# humanoid-11.net
KiCad netlist of a schematic drawn in EAGLE
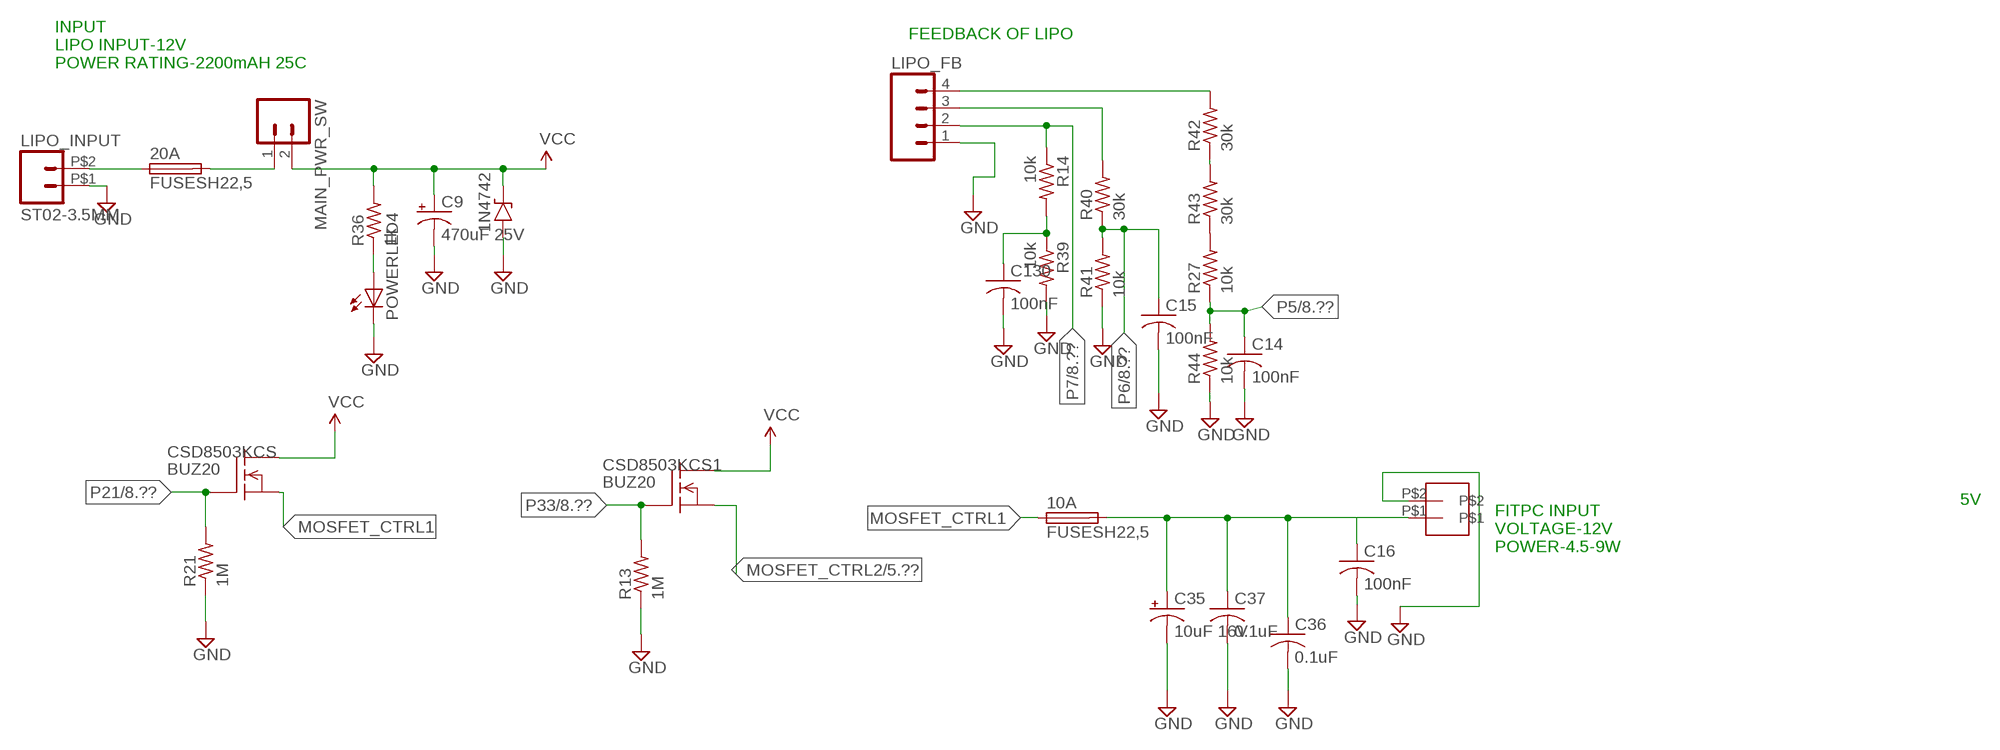
[diagram p0: schematic, sheet 1]
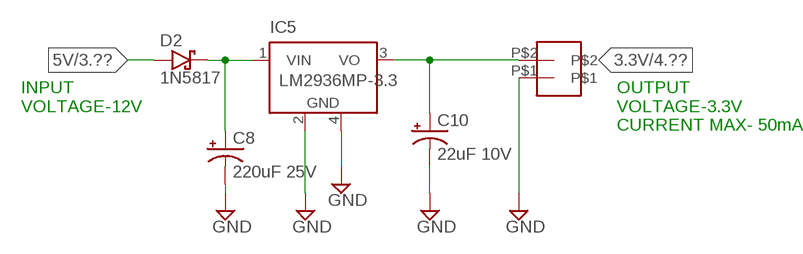
[diagram p1: schematic, sheet 2]
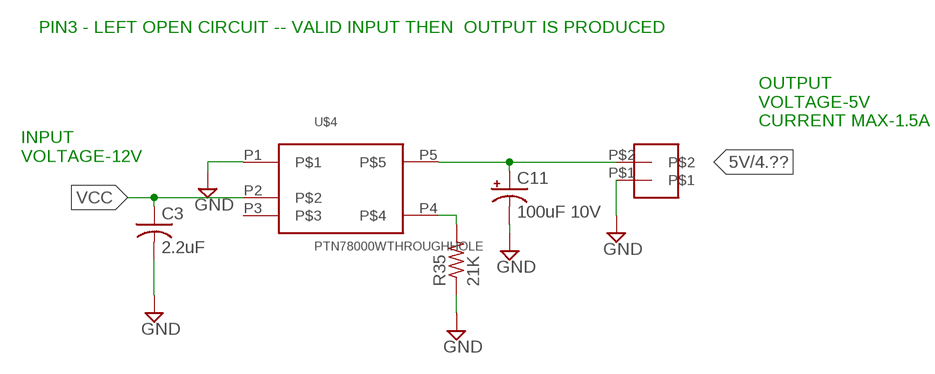
[diagram p2: schematic, sheet 3]
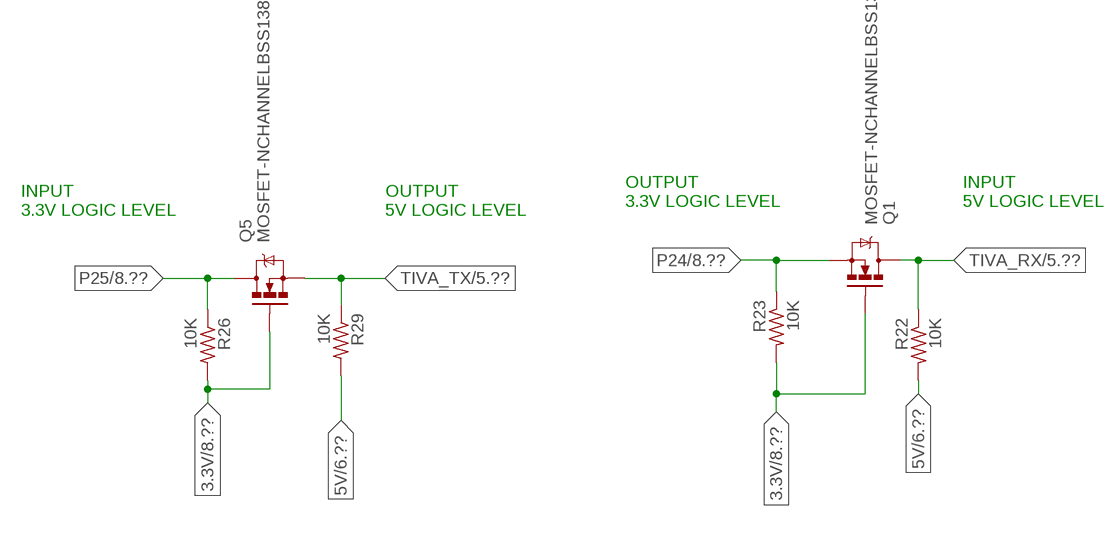
[diagram p3: schematic, sheet 4]
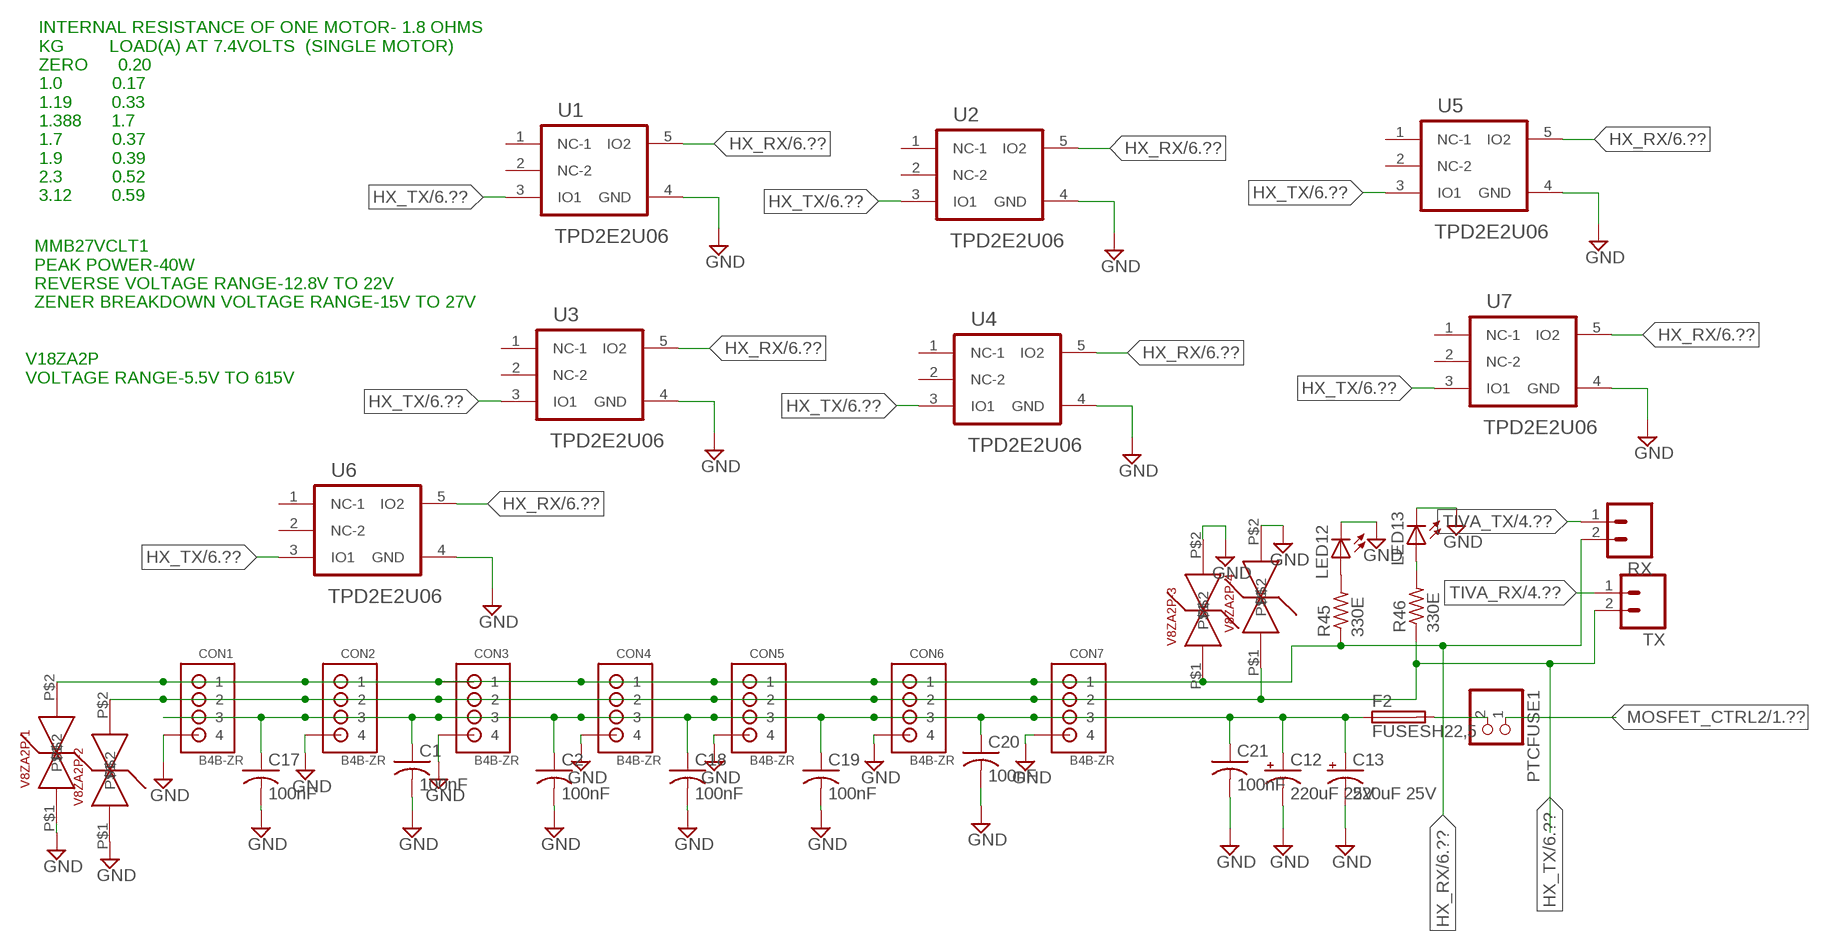
[diagram p4: schematic, sheet 5]
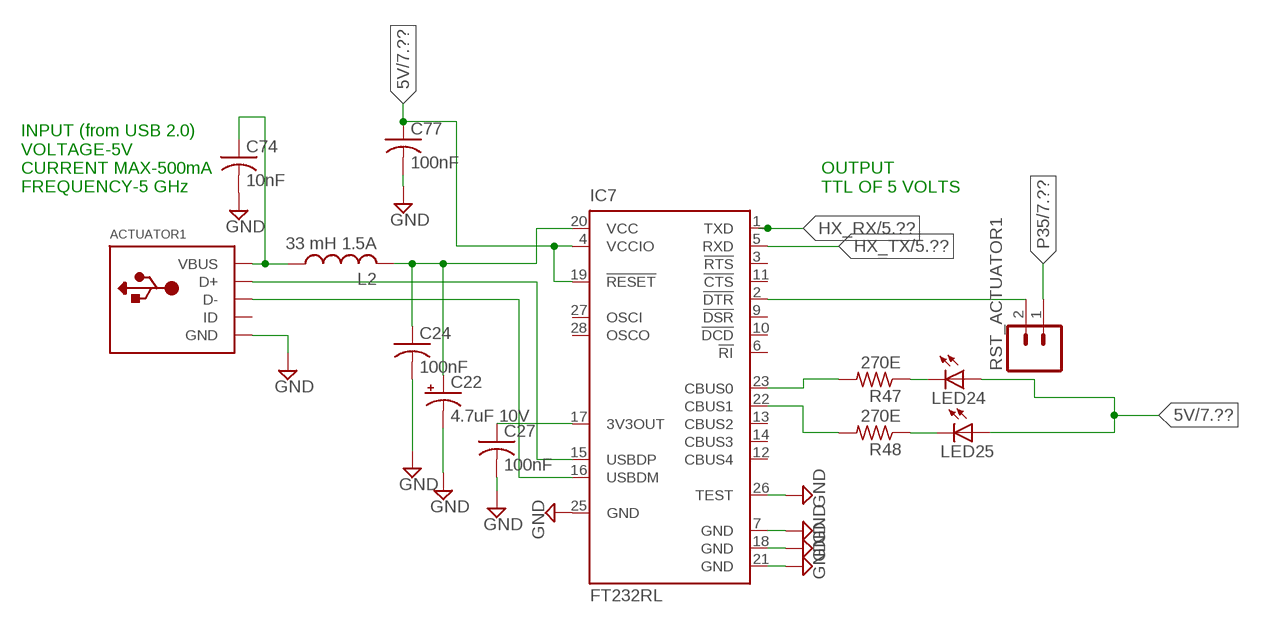
[diagram p5: schematic, sheet 6]
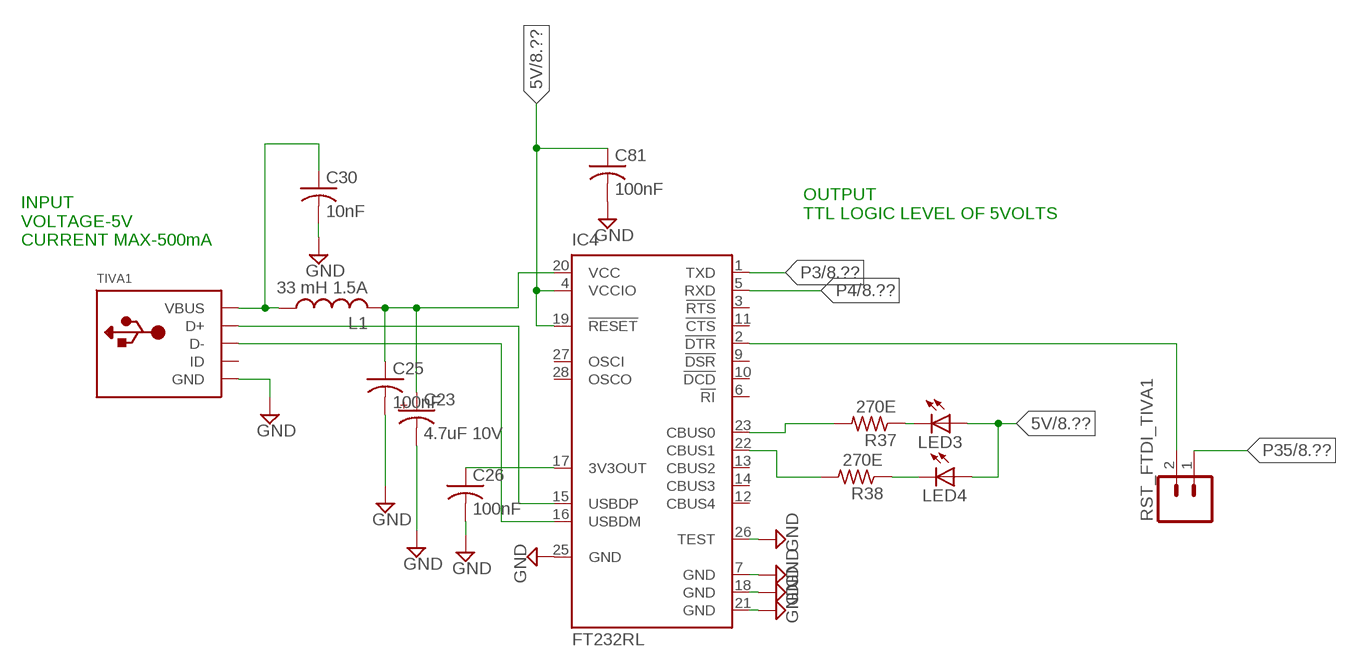
[diagram p6: schematic, sheet 7]
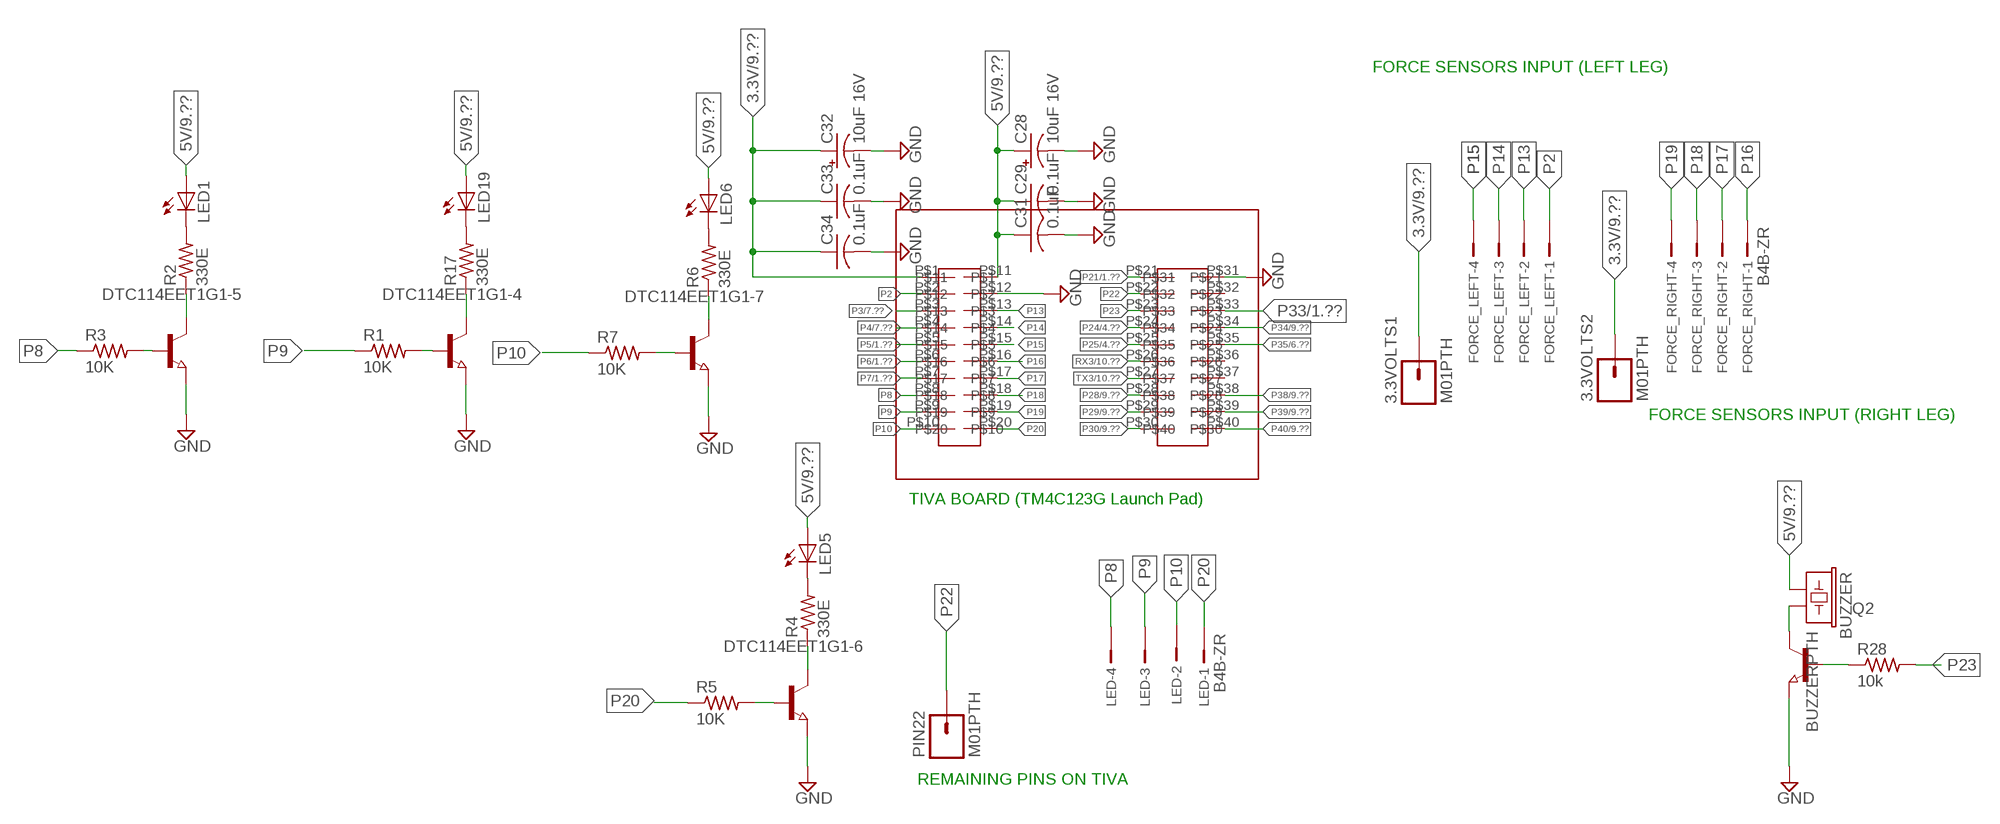
[diagram p7: schematic, sheet 8]
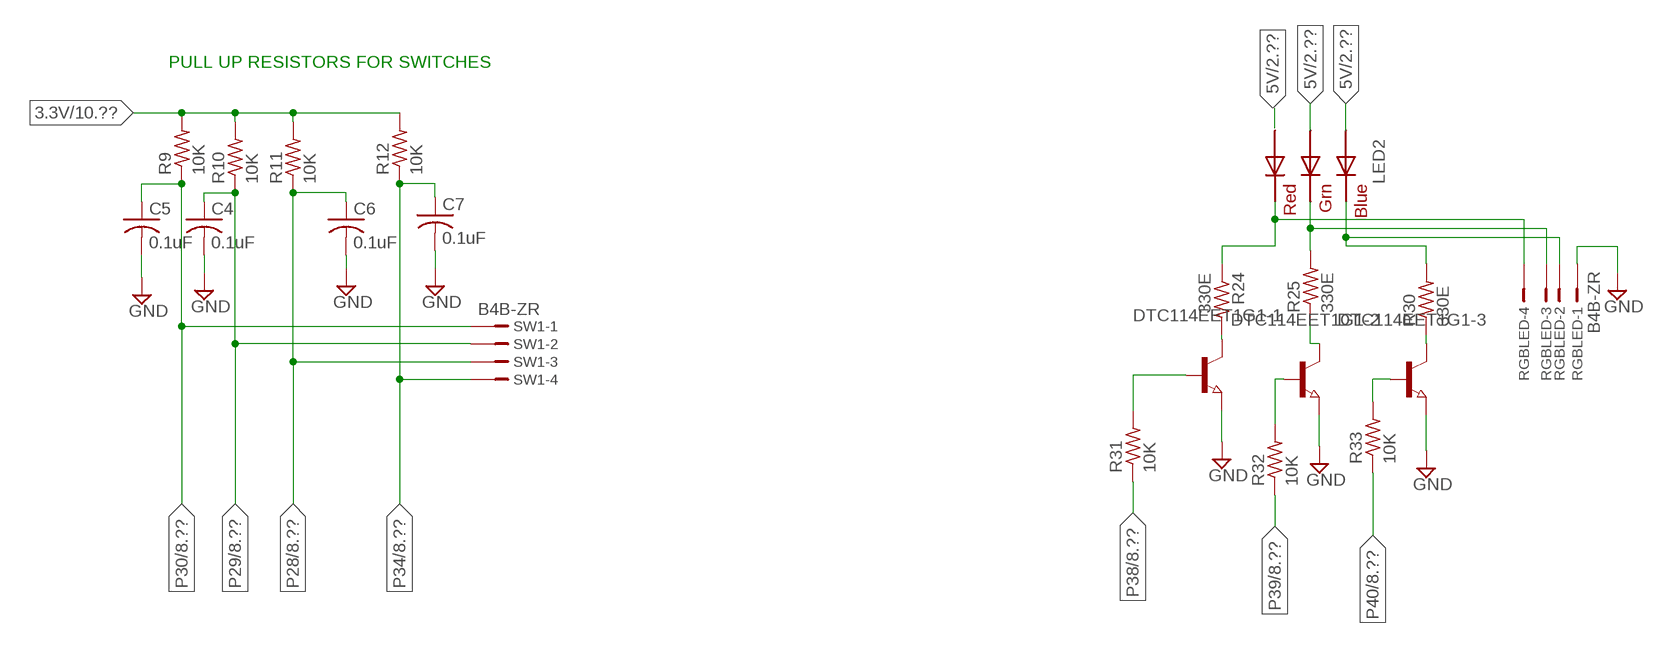
[diagram p8: schematic, sheet 9]
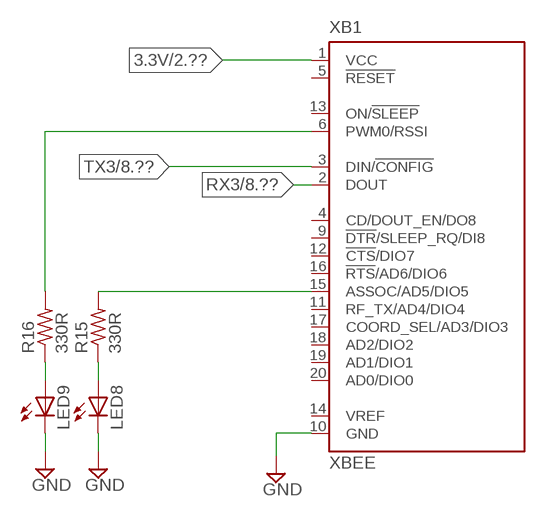
[diagram p9: schematic, sheet 10]

(export (version "E")
  (design (tool "Eeschema 10.0.6"))
  (components
    (comp (ref "5V1")
      (value "2PINRIGHT")
      (footprint "eagle-import:2PINRIGHT")
      (libsource (lib "eagle-import") (part "2PINRIGHT"))
    )
    (comp (ref "C3")
      (value "2.2uF")
      (footprint "eagle-import:C1608")
      (fields
        (field (name "MANUFACTURER") "TDK")
        (field (name "MOUSER_PARTNO") "810-C1608X7R1A225K")
        (field (name "PARTNO") "C1608X7R1A225K080AC")
      )
      (libsource (lib "eagle-import") (part "resistor_C-USC1608"))
    )
    (comp (ref "C11")
      (value "100uF 10V")
      (footprint "eagle-import:PANASONIC_E")
      (fields
        (field (name "MANUFACTURER") "Panasonic")
        (field (name "MOUSER_PARTNO") " 667-EEE-HA1A101P")
        (field (name "PARTNO") "EEE-HA1A101P")
      )
      (libsource (lib "eagle-import") (part "CPOL-USE"))
    )
    (comp (ref "R35")
      (value "21K")
      (footprint "eagle-import:R0805")
      (libsource (lib "eagle-import") (part "R-US_R0805"))
    )
    (comp (ref "U$4")
      (value "PTN78000WTHROUGHHOLE")
      (footprint "eagle-import:PTN78000W")
      (libsource (lib "eagle-import") (part "PTN78000WTHROUGHHOLE"))
    )
    (comp (ref "ACTUATOR1")
      (value "USBMINIB")
      (footprint "eagle-import:USB-MINIB")
      (libsource (lib "eagle-import") (part "USBMINIB"))
    )
    (comp (ref "C22")
      (value "4.7uF 10V")
      (footprint "eagle-import:PANASONIC_B")
      (fields
        (field (name "MANUFACTURER") "Panasonic")
        (field (name "MOUSER_PARTNO") "667-10SVP4R7M")
        (field (name "PARTNO") "10SVP4R7M")
      )
      (libsource (lib "eagle-import") (part "CPOL-USB"))
    )
    (comp (ref "C24")
      (value "100nF")
      (footprint "eagle-import:C1206")
      (fields (field (name "MANUFACTURER") "KEMET") (field (name "PARTNO") "C1206C104K5RACTU"))
      (libsource (lib "eagle-import") (part "C-USC1206"))
    )
    (comp (ref "C27")
      (value "100nF")
      (footprint "eagle-import:C1206")
      (fields (field (name "MANUFACTURER") "KEMET") (field (name "PARTNO") "C1206C104K5RACTU"))
      (libsource (lib "eagle-import") (part "C-USC1206"))
    )
    (comp (ref "C74")
      (value "10nF")
      (footprint "eagle-import:C1206")
      (libsource (lib "eagle-import") (part "C-USC1206"))
    )
    (comp (ref "C77")
      (value "100nF")
      (footprint "eagle-import:C1206")
      (libsource (lib "eagle-import") (part "C-USC1206"))
    )
    (comp (ref "IC7")
      (value "FT232RL")
      (footprint "eagle-import:SSOP28")
      (fields (field (name "OC_NEWARK") "unknown"))
      (libsource (lib "eagle-import") (part "FT232RL"))
    )
    (comp (ref "L2")
      (value "33 mH 1.5A")
      (footprint "eagle-import:L0805")
      (fields
        (field (name "MANUFACTURER") "Laird Technologies")
        (field (name "MOUSER_PARTNO") "875-MI0805K400R-10")
        (field (name "PARTNO") "MI0805K400R-10")
      )
      (libsource (lib "eagle-import") (part "L-USL0805"))
    )
    (comp (ref "LED24")
      (value "LEDCHIPLED_1206")
      (footprint "eagle-import:CHIPLED_1206")
      (libsource (lib "eagle-import") (part "LEDCHIPLED_1206"))
    )
    (comp (ref "LED25")
      (value "LEDCHIPLED_1206")
      (footprint "eagle-import:CHIPLED_1206")
      (libsource (lib "eagle-import") (part "LEDCHIPLED_1206"))
    )
    (comp (ref "R47")
      (value "270E")
      (footprint "eagle-import:R0805")
      (libsource (lib "eagle-import") (part "R-US_R0805"))
    )
    (comp (ref "R48")
      (value "270E")
      (footprint "eagle-import:R0805")
      (libsource (lib "eagle-import") (part "R-US_R0805"))
    )
    (comp (ref "RST_ACTUATOR1")
      (value "M02PTH")
      (footprint "eagle-import:1X02")
      (libsource (lib "eagle-import") (part "M02PTH"))
    )
    (comp (ref "3.3V1")
      (value "2PINRIGHT")
      (footprint "eagle-import:2PINRIGHT")
      (libsource (lib "eagle-import") (part "2PINRIGHT"))
    )
    (comp (ref "C8")
      (value "220uF 25V")
      (footprint "eagle-import:PANASONIC_G")
      (fields
        (field (name "MANUFACTURER") " PANASONIC ELECTRONIC COMPONENTS")
        (field (name "MOUSER_PARTNO") "667-EEE-1EA221P")
        (field (name "PARTNO") "EEE-1EA221P")
      )
      (libsource (lib "eagle-import") (part "CPOL-USG"))
    )
    (comp (ref "C10")
      (value "22uF 10V")
      (footprint "eagle-import:PANASONIC_B")
      (fields
        (field (name "MANUFACTURER") " PANASONIC ELECTRONIC COMPONENTS")
        (field (name "PARTNO") "EEEFK1A220AR")
      )
      (libsource (lib "eagle-import") (part "CPOL-USB"))
    )
    (comp (ref "D2")
      (value "1N5817")
      (footprint "eagle-import:DO41-3")
      (libsource (lib "eagle-import") (part "1N5817"))
    )
    (comp (ref "IC5")
      (value "LM2936MP-3.3")
      (footprint "eagle-import:SOT223")
      (fields
        (field (name "MF") "NATIONAL SEMICONDUCTOR")
        (field (name "MPN") "LM2936MP-3.3/NOPB")
        (field (name "OC_NEWARK") "unknown")
      )
      (libsource (lib "eagle-import") (part "LM2936MP?-3.3"))
    )
    (comp (ref "3.3VOLTS1")
      (value "M01PTH")
      (footprint "eagle-import:1X01")
      (libsource (lib "eagle-import") (part "M01PTH"))
    )
    (comp (ref "3.3VOLTS2")
      (value "M01PTH")
      (footprint "eagle-import:1X01")
      (libsource (lib "eagle-import") (part "M01PTH"))
    )
    (comp (ref "BUZZER")
      (value "BUZZERPTH")
      (footprint "eagle-import:BUZZER-12MM")
      (libsource (lib "eagle-import") (part "BUZZERPTH"))
    )
    (comp (ref "C28")
      (value "10uF 16V")
      (footprint "eagle-import:PANASONIC_B")
      (libsource (lib "eagle-import") (part "CPOL-USB"))
    )
    (comp (ref "C29")
      (value "0.1uF")
      (footprint "eagle-import:C0805")
      (libsource (lib "eagle-import") (part "resistor_C-USC0805"))
    )
    (comp (ref "C31")
      (value "0.1uF")
      (footprint "eagle-import:C0805")
      (libsource (lib "eagle-import") (part "resistor_C-USC0805"))
    )
    (comp (ref "C32")
      (value "10uF 16V")
      (footprint "eagle-import:PANASONIC_B")
      (libsource (lib "eagle-import") (part "CPOL-USB"))
    )
    (comp (ref "C33")
      (value "0.1uF")
      (footprint "eagle-import:C0805")
      (libsource (lib "eagle-import") (part "resistor_C-USC0805"))
    )
    (comp (ref "C34")
      (value "0.1uF")
      (footprint "eagle-import:C0805")
      (libsource (lib "eagle-import") (part "resistor_C-USC0805"))
    )
    (comp (ref "DTC114EET1G1-4")
      (value "NPN-TRANSISTOR_SOT23")
      (footprint "eagle-import:SOT23")
      (libsource (lib "eagle-import") (part "NPN-TRANSISTOR_SOT23"))
    )
    (comp (ref "DTC114EET1G1-5")
      (value "NPN-TRANSISTOR_SOT23")
      (footprint "eagle-import:SOT23")
      (libsource (lib "eagle-import") (part "NPN-TRANSISTOR_SOT23"))
    )
    (comp (ref "DTC114EET1G1-6")
      (value "NPN-TRANSISTOR_SOT23")
      (footprint "eagle-import:SOT23")
      (libsource (lib "eagle-import") (part "NPN-TRANSISTOR_SOT23"))
    )
    (comp (ref "DTC114EET1G1-7")
      (value "NPN-TRANSISTOR_SOT23")
      (footprint "eagle-import:SOT23")
      (libsource (lib "eagle-import") (part "NPN-TRANSISTOR_SOT23"))
    )
    (comp (ref "FORCE_LEFT")
      (value "B4B-ZR")
      (footprint "eagle-import:B4B-ZR")
      (fields
        (field (name "MF") "FARNELL")
        (field (name "MPN") "B4B-ZR(LF)(SN)")
        (field (name "OC_NEWARK") "unknown")
      )
      (libsource (lib "eagle-import") (part "?4B-ZRB"))
    )
    (comp (ref "FORCE_RIGHT")
      (value "B4B-ZR")
      (footprint "eagle-import:B4B-ZR")
      (fields
        (field (name "MF") "FARNELL")
        (field (name "MPN") "B4B-ZR(LF)(SN)")
        (field (name "OC_NEWARK") "unknown")
      )
      (libsource (lib "eagle-import") (part "?4B-ZRB"))
    )
    (comp (ref "LED")
      (value "B4B-ZR")
      (footprint "eagle-import:B4B-ZR")
      (fields
        (field (name "MF") "FARNELL")
        (field (name "MPN") "B4B-ZR(LF)(SN)")
        (field (name "OC_NEWARK") "unknown")
      )
      (libsource (lib "eagle-import") (part "?4B-ZRB"))
    )
    (comp (ref "LED1")
      (value "LEDCHIPLED_1206")
      (footprint "eagle-import:CHIPLED_1206")
      (libsource (lib "eagle-import") (part "LEDCHIPLED_1206"))
    )
    (comp (ref "LED5")
      (value "LEDCHIPLED_1206")
      (footprint "eagle-import:CHIPLED_1206")
      (libsource (lib "eagle-import") (part "LEDCHIPLED_1206"))
    )
    (comp (ref "LED6")
      (value "LEDCHIPLED_1206")
      (footprint "eagle-import:CHIPLED_1206")
      (libsource (lib "eagle-import") (part "LEDCHIPLED_1206"))
    )
    (comp (ref "LED19")
      (value "LEDCHIPLED_1206")
      (footprint "eagle-import:CHIPLED_1206")
      (libsource (lib "eagle-import") (part "LEDCHIPLED_1206"))
    )
    (comp (ref "PIN22")
      (value "M01PTH")
      (footprint "eagle-import:1X01")
      (libsource (lib "eagle-import") (part "M01PTH"))
    )
    (comp (ref "Q2")
      (value "NPN-TRANSISTOR_SOT23")
      (footprint "eagle-import:SOT23")
      (libsource (lib "eagle-import") (part "NPN-TRANSISTOR_SOT23"))
    )
    (comp (ref "R1")
      (value "10K")
      (footprint "eagle-import:R0805")
      (libsource (lib "eagle-import") (part "R-US_R0805"))
    )
    (comp (ref "R2")
      (value "330E")
      (footprint "eagle-import:R0805")
      (libsource (lib "eagle-import") (part "R-US_R0805"))
    )
    (comp (ref "R3")
      (value "10K")
      (footprint "eagle-import:R0805")
      (libsource (lib "eagle-import") (part "R-US_R0805"))
    )
    (comp (ref "R4")
      (value "330E")
      (footprint "eagle-import:R0805")
      (libsource (lib "eagle-import") (part "R-US_R0805"))
    )
    (comp (ref "R5")
      (value "10K")
      (footprint "eagle-import:R0805")
      (libsource (lib "eagle-import") (part "R-US_R0805"))
    )
    (comp (ref "R6")
      (value "330E")
      (footprint "eagle-import:R0805")
      (libsource (lib "eagle-import") (part "R-US_R0805"))
    )
    (comp (ref "R7")
      (value "10K")
      (footprint "eagle-import:R0805")
      (libsource (lib "eagle-import") (part "R-US_R0805"))
    )
    (comp (ref "R17")
      (value "330E")
      (footprint "eagle-import:R0805")
      (libsource (lib "eagle-import") (part "R-US_R0805"))
    )
    (comp (ref "R28")
      (value "10k")
      (footprint "eagle-import:R0805")
      (libsource (lib "eagle-import") (part "R-US_R0805"))
    )
    (comp (ref "U$1")
      (value "TIVA")
      (footprint "eagle-import:TIVA")
      (libsource (lib "eagle-import") (part "TIVA"))
    )
    (comp (ref "LED8")
      (value "LEDCHIPLED_1206")
      (footprint "eagle-import:CHIPLED_1206")
      (libsource (lib "eagle-import") (part "LEDCHIPLED_1206"))
    )
    (comp (ref "LED9")
      (value "LEDCHIPLED_1206")
      (footprint "eagle-import:CHIPLED_1206")
      (libsource (lib "eagle-import") (part "LEDCHIPLED_1206"))
    )
    (comp (ref "R15")
      (value "330R")
      (footprint "eagle-import:R0805")
      (libsource (lib "eagle-import") (part "R-US_R0805"))
    )
    (comp (ref "R16")
      (value "330R")
      (footprint "eagle-import:R0805")
      (libsource (lib "eagle-import") (part "R-US_R0805"))
    )
    (comp (ref "XB1")
      (value "XBEE")
      (footprint "eagle-import:XBEE")
      (fields (field (name "MPN") "XBP24-Z7UIT-004"))
      (libsource (lib "eagle-import") (part "XBEE"))
    )
    (comp (ref "Q1")
      (value "MOSFET-NCHANNELBSS138")
      (footprint "eagle-import:SOT23")
      (libsource (lib "eagle-import") (part "MOSFET-NCHANNELBSS138"))
    )
    (comp (ref "Q5")
      (value "MOSFET-NCHANNELBSS138")
      (footprint "eagle-import:SOT23")
      (libsource (lib "eagle-import") (part "MOSFET-NCHANNELBSS138"))
    )
    (comp (ref "R22")
      (value "10K")
      (footprint "eagle-import:R0805")
      (libsource (lib "eagle-import") (part "R-US_R0805"))
    )
    (comp (ref "R23")
      (value "10K")
      (footprint "eagle-import:R0805")
      (libsource (lib "eagle-import") (part "R-US_R0805"))
    )
    (comp (ref "R26")
      (value "10K")
      (footprint "eagle-import:R0805")
      (libsource (lib "eagle-import") (part "R-US_R0805"))
    )
    (comp (ref "R29")
      (value "10K")
      (footprint "eagle-import:R0805")
      (libsource (lib "eagle-import") (part "R-US_R0805"))
    )
    (comp (ref "C4")
      (value "0.1uF")
      (footprint "eagle-import:C1206")
      (fields
        (field (name "MANUFACTURER") "Kemet")
        (field (name "MOUSER_PARTNO") "80-C0805C104M5R")
        (field (name "PARTNO") "C0805C104M5RACTU")
      )
      (libsource (lib "eagle-import") (part "C-USC1206"))
    )
    (comp (ref "C5")
      (value "0.1uF")
      (footprint "eagle-import:C1206")
      (fields
        (field (name "MANUFACTURER") "Kemet")
        (field (name "MOUSER_PARTNO") "80-C0805C104M5R")
        (field (name "PARTNO") "C0805C104M5RACTU")
      )
      (libsource (lib "eagle-import") (part "C-USC1206"))
    )
    (comp (ref "C6")
      (value "0.1uF")
      (footprint "eagle-import:C1206")
      (fields
        (field (name "MANUFACTURER") "Kemet")
        (field (name "MOUSER_PARTNO") "80-C0805C104M5R")
        (field (name "PARTNO") "C0805C104M5RACTU")
      )
      (libsource (lib "eagle-import") (part "C-USC1206"))
    )
    (comp (ref "C7")
      (value "0.1uF")
      (footprint "eagle-import:C1206")
      (fields
        (field (name "MANUFACTURER") "Kemet")
        (field (name "MOUSER_PARTNO") "80-C0805C104M5R")
        (field (name "PARTNO") "C0805C104M5RACTU")
      )
      (libsource (lib "eagle-import") (part "C-USC1206"))
    )
    (comp (ref "DTC114EET1G1-1")
      (value "NPN-TRANSISTOR_SOT23")
      (footprint "eagle-import:SOT23")
      (libsource (lib "eagle-import") (part "NPN-TRANSISTOR_SOT23"))
    )
    (comp (ref "DTC114EET1G1-2")
      (value "NPN-TRANSISTOR_SOT23")
      (footprint "eagle-import:SOT23")
      (libsource (lib "eagle-import") (part "NPN-TRANSISTOR_SOT23"))
    )
    (comp (ref "DTC114EET1G1-3")
      (value "NPN-TRANSISTOR_SOT23")
      (footprint "eagle-import:SOT23")
      (libsource (lib "eagle-import") (part "NPN-TRANSISTOR_SOT23"))
    )
    (comp (ref "LED2")
      (value "RGBLED5050")
      (footprint "eagle-import:RGBLED5050")
      (libsource (lib "eagle-import") (part "RGBLED5050"))
    )
    (comp (ref "R9")
      (value "10K")
      (footprint "eagle-import:R0805")
      (libsource (lib "eagle-import") (part "R-US_R0805"))
    )
    (comp (ref "R10")
      (value "10K")
      (footprint "eagle-import:R0805")
      (libsource (lib "eagle-import") (part "R-US_R0805"))
    )
    (comp (ref "R11")
      (value "10K")
      (footprint "eagle-import:R0805")
      (libsource (lib "eagle-import") (part "R-US_R0805"))
    )
    (comp (ref "R12")
      (value "10K")
      (footprint "eagle-import:R0805")
      (libsource (lib "eagle-import") (part "R-US_R0805"))
    )
    (comp (ref "R24")
      (value "330E")
      (footprint "eagle-import:R0805")
      (libsource (lib "eagle-import") (part "R-US_R0805"))
    )
    (comp (ref "R25")
      (value "330E")
      (footprint "eagle-import:R0805")
      (libsource (lib "eagle-import") (part "R-US_R0805"))
    )
    (comp (ref "R30")
      (value "330E")
      (footprint "eagle-import:R0805")
      (libsource (lib "eagle-import") (part "R-US_R0805"))
    )
    (comp (ref "R31")
      (value "10K")
      (footprint "eagle-import:R0805")
      (libsource (lib "eagle-import") (part "R-US_R0805"))
    )
    (comp (ref "R32")
      (value "10K")
      (footprint "eagle-import:R0805")
      (libsource (lib "eagle-import") (part "R-US_R0805"))
    )
    (comp (ref "R33")
      (value "10K")
      (footprint "eagle-import:R0805")
      (libsource (lib "eagle-import") (part "R-US_R0805"))
    )
    (comp (ref "RGBLED")
      (value "B4B-ZR")
      (footprint "eagle-import:B4B-ZR")
      (fields
        (field (name "MF") "FARNELL")
        (field (name "MPN") "B4B-ZR(LF)(SN)")
        (field (name "OC_NEWARK") "unknown")
      )
      (libsource (lib "eagle-import") (part "?4B-ZRB"))
    )
    (comp (ref "SW1")
      (value "B4B-ZR")
      (footprint "eagle-import:B4B-ZR")
      (fields
        (field (name "MF") "FARNELL")
        (field (name "MPN") "B4B-ZR(LF)(SN)")
        (field (name "OC_NEWARK") "unknown")
      )
      (libsource (lib "eagle-import") (part "?4B-ZRB"))
    )
    (comp (ref "C23")
      (value "4.7uF 10V")
      (footprint "eagle-import:PANASONIC_B")
      (fields
        (field (name "MANUFACTURER") "Panasonic")
        (field (name "MOUSER_PARTNO") "667-10SVP4R7M")
        (field (name "PARTNO") "10SVP4R7M")
      )
      (libsource (lib "eagle-import") (part "CPOL-USB"))
    )
    (comp (ref "C25")
      (value "100nF")
      (footprint "eagle-import:C1206")
      (fields (field (name "MANUFACTURER") "KEMET") (field (name "PARTNO") "C1206C104K5RACTU"))
      (libsource (lib "eagle-import") (part "C-USC1206"))
    )
    (comp (ref "C26")
      (value "100nF")
      (footprint "eagle-import:C1206")
      (fields (field (name "MANUFACTURER") "KEMET") (field (name "PARTNO") "C1206C104K5RACTU"))
      (libsource (lib "eagle-import") (part "C-USC1206"))
    )
    (comp (ref "C30")
      (value "10nF")
      (footprint "eagle-import:C1206")
      (libsource (lib "eagle-import") (part "C-USC1206"))
    )
    (comp (ref "C81")
      (value "100nF")
      (footprint "eagle-import:C1206")
      (libsource (lib "eagle-import") (part "C-USC1206"))
    )
    (comp (ref "IC4")
      (value "FT232RL")
      (footprint "eagle-import:SSOP28")
      (fields (field (name "OC_NEWARK") "unknown"))
      (libsource (lib "eagle-import") (part "FT232RL"))
    )
    (comp (ref "L1")
      (value "33 mH 1.5A")
      (footprint "eagle-import:L0805")
      (fields
        (field (name "MANUFACTURER") "Laird Technologies")
        (field (name "MOUSER_PARTNO") "875-MI0805K400R-10")
        (field (name "PARTNO") "MI0805K400R-10")
      )
      (libsource (lib "eagle-import") (part "L-USL0805"))
    )
    (comp (ref "LED3")
      (value "LEDCHIPLED_1206")
      (footprint "eagle-import:CHIPLED_1206")
      (libsource (lib "eagle-import") (part "LEDCHIPLED_1206"))
    )
    (comp (ref "LED4")
      (value "LEDCHIPLED_1206")
      (footprint "eagle-import:CHIPLED_1206")
      (libsource (lib "eagle-import") (part "LEDCHIPLED_1206"))
    )
    (comp (ref "R37")
      (value "270E")
      (footprint "eagle-import:R0805")
      (libsource (lib "eagle-import") (part "R-US_R0805"))
    )
    (comp (ref "R38")
      (value "270E")
      (footprint "eagle-import:R0805")
      (libsource (lib "eagle-import") (part "R-US_R0805"))
    )
    (comp (ref "RST_FTDI_TIVA1")
      (value "M02PTH")
      (footprint "eagle-import:1X02")
      (libsource (lib "eagle-import") (part "M02PTH"))
    )
    (comp (ref "TIVA1")
      (value "USBMINIB")
      (footprint "eagle-import:USB-MINIB")
      (libsource (lib "eagle-import") (part "USBMINIB"))
    )
    (comp (ref "C1")
      (value "100nF")
      (footprint "eagle-import:C1206")
      (fields (field (name "MANUFACTURER") "KEMET") (field (name "PARTNO") "C1206C104K5RACTU"))
      (libsource (lib "eagle-import") (part "C-USC1206"))
    )
    (comp (ref "C2")
      (value "100nF")
      (footprint "eagle-import:C1206")
      (fields (field (name "MANUFACTURER") "KEMET") (field (name "PARTNO") "C1206C104K5RACTU"))
      (libsource (lib "eagle-import") (part "C-USC1206"))
    )
    (comp (ref "C12")
      (value "220uF 25V")
      (footprint "eagle-import:PANASONIC_G")
      (fields
        (field (name "MANUFACTURER") " PANASONIC ELECTRONIC COMPONENTS")
        (field (name "MOUSER_PARTNO") "667-EEE-1EA221P")
        (field (name "PARTNO") "EEE-1EA221P")
      )
      (libsource (lib "eagle-import") (part "CPOL-USG"))
    )
    (comp (ref "C13")
      (value "220uF 25V")
      (footprint "eagle-import:PANASONIC_G")
      (fields
        (field (name "MANUFACTURER") " PANASONIC ELECTRONIC COMPONENTS")
        (field (name "MOUSER_PARTNO") "667-EEE-1EA221P")
        (field (name "PARTNO") "EEE-1EA221P")
      )
      (libsource (lib "eagle-import") (part "CPOL-USG"))
    )
    (comp (ref "C17")
      (value "100nF")
      (footprint "eagle-import:C1206")
      (fields (field (name "MANUFACTURER") "KEMET") (field (name "PARTNO") "C1206C104K5RACTU"))
      (libsource (lib "eagle-import") (part "C-USC1206"))
    )
    (comp (ref "C18")
      (value "100nF")
      (footprint "eagle-import:C1206")
      (fields (field (name "MANUFACTURER") "KEMET") (field (name "PARTNO") "C1206C104K5RACTU"))
      (libsource (lib "eagle-import") (part "C-USC1206"))
    )
    (comp (ref "C19")
      (value "100nF")
      (footprint "eagle-import:C1206")
      (fields (field (name "MANUFACTURER") "KEMET") (field (name "PARTNO") "C1206C104K5RACTU"))
      (libsource (lib "eagle-import") (part "C-USC1206"))
    )
    (comp (ref "C20")
      (value "100nF")
      (footprint "eagle-import:C1206")
      (fields (field (name "MANUFACTURER") "KEMET") (field (name "PARTNO") "C1206C104K5RACTU"))
      (libsource (lib "eagle-import") (part "C-USC1206"))
    )
    (comp (ref "C21")
      (value "100nF")
      (footprint "eagle-import:C1206")
      (fields (field (name "MANUFACTURER") "KEMET") (field (name "PARTNO") "C1206C104K5RACTU"))
      (libsource (lib "eagle-import") (part "C-USC1206"))
    )
    (comp (ref "CON1")
      (value "B4B-ZR")
      (footprint "eagle-import:B4B-ZR")
      (fields (field (name "MF") "FARNELL") (field (name "MPN") "B4B-ZR(LF)(SN)"))
      (libsource (lib "eagle-import") (part "B4B-ZR"))
    )
    (comp (ref "CON2")
      (value "B4B-ZR")
      (footprint "eagle-import:B4B-ZR")
      (fields (field (name "MF") "FARNELL") (field (name "MPN") "B4B-ZR(LF)(SN)"))
      (libsource (lib "eagle-import") (part "B4B-ZR"))
    )
    (comp (ref "CON3")
      (value "B4B-ZR")
      (footprint "eagle-import:B4B-ZR")
      (fields (field (name "MF") "FARNELL") (field (name "MPN") "B4B-ZR(LF)(SN)"))
      (libsource (lib "eagle-import") (part "B4B-ZR"))
    )
    (comp (ref "CON4")
      (value "B4B-ZR")
      (footprint "eagle-import:B4B-ZR")
      (fields (field (name "MF") "FARNELL") (field (name "MPN") "B4B-ZR(LF)(SN)"))
      (libsource (lib "eagle-import") (part "B4B-ZR"))
    )
    (comp (ref "CON5")
      (value "B4B-ZR")
      (footprint "eagle-import:B4B-ZR")
      (fields (field (name "MF") "FARNELL") (field (name "MPN") "B4B-ZR(LF)(SN)"))
      (libsource (lib "eagle-import") (part "B4B-ZR"))
    )
    (comp (ref "CON6")
      (value "B4B-ZR")
      (footprint "eagle-import:B4B-ZR")
      (fields (field (name "MF") "FARNELL") (field (name "MPN") "B4B-ZR(LF)(SN)"))
      (libsource (lib "eagle-import") (part "B4B-ZR"))
    )
    (comp (ref "CON7")
      (value "B4B-ZR")
      (footprint "eagle-import:B4B-ZR")
      (fields (field (name "MF") "FARNELL") (field (name "MPN") "B4B-ZR(LF)(SN)"))
      (libsource (lib "eagle-import") (part "B4B-ZR"))
    )
    (comp (ref "F2")
      (value "FUSESH22,5")
      (footprint "eagle-import:SH22,5")
      (libsource (lib "eagle-import") (part "FUSESH22,5"))
    )
    (comp (ref "LED12")
      (value "LEDCHIPLED_1206")
      (footprint "eagle-import:CHIPLED_1206")
      (libsource (lib "eagle-import") (part "LEDCHIPLED_1206"))
    )
    (comp (ref "LED13")
      (value "LEDCHIPLED_1206")
      (footprint "eagle-import:CHIPLED_1206")
      (libsource (lib "eagle-import") (part "LEDCHIPLED_1206"))
    )
    (comp (ref "PTCFUSE1")
      (value "PINHD-1X2")
      (footprint "eagle-import:1X02")
      (libsource (lib "eagle-import") (part "PINHD-1X2"))
    )
    (comp (ref "R45")
      (value "330E")
      (footprint "eagle-import:R0805")
      (libsource (lib "eagle-import") (part "R-US_R0805"))
    )
    (comp (ref "R46")
      (value "330E")
      (footprint "eagle-import:R0805")
      (libsource (lib "eagle-import") (part "R-US_R0805"))
    )
    (comp (ref "RX")
      (value "M02PTH")
      (footprint "eagle-import:1X02")
      (libsource (lib "eagle-import") (part "M02PTH"))
    )
    (comp (ref "TX")
      (value "M02PTH")
      (footprint "eagle-import:1X02")
      (libsource (lib "eagle-import") (part "M02PTH"))
    )
    (comp (ref "U1")
      (value "TPD2E2U06")
      (footprint "eagle-import:SOT50P160X60-5N")
      (fields (field (name "MPN") "TPD2E001IDRLRQ1"))
      (libsource (lib "eagle-import") (part "TPD2E2U06"))
    )
    (comp (ref "U2")
      (value "TPD2E2U06")
      (footprint "eagle-import:SOT50P160X60-5N")
      (fields (field (name "MPN") "TPD2E001IDRLRQ1"))
      (libsource (lib "eagle-import") (part "TPD2E2U06"))
    )
    (comp (ref "U3")
      (value "TPD2E2U06")
      (footprint "eagle-import:SOT50P160X60-5N")
      (fields (field (name "MPN") "TPD2E001IDRLRQ1"))
      (libsource (lib "eagle-import") (part "TPD2E2U06"))
    )
    (comp (ref "U4")
      (value "TPD2E2U06")
      (footprint "eagle-import:SOT50P160X60-5N")
      (fields (field (name "MPN") "TPD2E001IDRLRQ1"))
      (libsource (lib "eagle-import") (part "TPD2E2U06"))
    )
    (comp (ref "U5")
      (value "TPD2E2U06")
      (footprint "eagle-import:SOT50P160X60-5N")
      (fields (field (name "MPN") "TPD2E001IDRLRQ1"))
      (libsource (lib "eagle-import") (part "TPD2E2U06"))
    )
    (comp (ref "U6")
      (value "TPD2E2U06")
      (footprint "eagle-import:SOT50P160X60-5N")
      (fields (field (name "MPN") "TPD2E001IDRLRQ1"))
      (libsource (lib "eagle-import") (part "TPD2E2U06"))
    )
    (comp (ref "U7")
      (value "TPD2E2U06")
      (footprint "eagle-import:SOT50P160X60-5N")
      (fields (field (name "MPN") "TPD2E001IDRLRQ1"))
      (libsource (lib "eagle-import") (part "TPD2E2U06"))
    )
    (comp (ref "V8ZA2P-1")
      (value "V18ZA2P")
      (footprint "eagle-import:V18ZA2P")
      (libsource (lib "eagle-import") (part "V18ZA2P"))
    )
    (comp (ref "V8ZA2P-2")
      (value "V18ZA2P")
      (footprint "eagle-import:V18ZA2P")
      (libsource (lib "eagle-import") (part "V18ZA2P"))
    )
    (comp (ref "V8ZA2P-3")
      (value "V18ZA2P")
      (footprint "eagle-import:V18ZA2P")
      (libsource (lib "eagle-import") (part "V18ZA2P"))
    )
    (comp (ref "V8ZA2P-4")
      (value "V18ZA2P")
      (footprint "eagle-import:V18ZA2P")
      (libsource (lib "eagle-import") (part "V18ZA2P"))
    )
    (comp (ref "1N4742")
      (value "1N47XX3")
      (footprint "eagle-import:DO41-3")
      (libsource (lib "eagle-import") (part "1N47XX3"))
    )
    (comp (ref "10A")
      (value "FUSESH22,5")
      (footprint "eagle-import:SH22,5")
      (libsource (lib "eagle-import") (part "FUSESH22,5"))
    )
    (comp (ref "20A")
      (value "FUSESH22,5")
      (footprint "eagle-import:SH22,5")
      (libsource (lib "eagle-import") (part "FUSESH22,5"))
    )
    (comp (ref "C9")
      (value "470uF 25V")
      (footprint "eagle-import:PANASONIC_G")
      (fields
        (field (name "MANUFACTURER") " PANASONIC ELECTRONIC COMPONENTS")
        (field (name "PARTNO") "EEEFK1E471AP")
      )
      (libsource (lib "eagle-import") (part "CPOL-USG"))
    )
    (comp (ref "C14")
      (value "100nF")
      (footprint "eagle-import:C1206")
      (fields (field (name "MANUFACTURER") "KEMET") (field (name "PARTNO") "C1206C104K5RACTU"))
      (libsource (lib "eagle-import") (part "C-USC1206"))
    )
    (comp (ref "C15")
      (value "100nF")
      (footprint "eagle-import:C1206")
      (fields (field (name "MANUFACTURER") "KEMET") (field (name "PARTNO") "C1206C104K5RACTU"))
      (libsource (lib "eagle-import") (part "C-USC1206"))
    )
    (comp (ref "C16")
      (value "100nF")
      (footprint "eagle-import:C1206")
      (fields (field (name "MANUFACTURER") "KEMET") (field (name "PARTNO") "C1206C104K5RACTU"))
      (libsource (lib "eagle-import") (part "C-USC1206"))
    )
    (comp (ref "C35")
      (value "10uF 16V")
      (footprint "eagle-import:PANASONIC_B")
      (libsource (lib "eagle-import") (part "CPOL-USB"))
    )
    (comp (ref "C36")
      (value "0.1uF")
      (footprint "eagle-import:C0805")
      (libsource (lib "eagle-import") (part "resistor_C-USC0805"))
    )
    (comp (ref "C37")
      (value "0.1uF")
      (footprint "eagle-import:C0805")
      (libsource (lib "eagle-import") (part "resistor_C-USC0805"))
    )
    (comp (ref "C130")
      (value "100nF")
      (footprint "eagle-import:C1206")
      (fields (field (name "MANUFACTURER") "KEMET") (field (name "PARTNO") "C1206C104K5RACTU"))
      (libsource (lib "eagle-import") (part "C-USC1206"))
    )
    (comp (ref "CSD8503KCS")
      (value "BUZ20")
      (footprint "eagle-import:TO220")
      (libsource (lib "eagle-import") (part "BUZ20"))
    )
    (comp (ref "CSD8503KCS1")
      (value "BUZ20")
      (footprint "eagle-import:TO220")
      (libsource (lib "eagle-import") (part "BUZ20"))
    )
    (comp (ref "FITPC")
      (value "2PINRIGHT")
      (footprint "eagle-import:2PINRIGHT")
      (libsource (lib "eagle-import") (part "2PINRIGHT"))
    )
    (comp (ref "LIPO_FB")
      (value "M04PTH")
      (footprint "eagle-import:1X04")
      (libsource (lib "eagle-import") (part "M04PTH"))
    )
    (comp (ref "LIPO_INPUT")
      (value "ST02-3.5MM")
      (footprint "eagle-import:ED350V-02P")
      (libsource (lib "eagle-import") (part "ST02-3.5MM"))
    )
    (comp (ref "MAIN_PWR_SW")
      (value "M02PTH")
      (footprint "eagle-import:1X02")
      (libsource (lib "eagle-import") (part "M02PTH"))
    )
    (comp (ref "POWERLED4")
      (value "LEDCHIPLED_1206")
      (footprint "eagle-import:CHIPLED_1206")
      (libsource (lib "eagle-import") (part "LEDCHIPLED_1206"))
    )
    (comp (ref "R13")
      (value "1M")
      (footprint "eagle-import:R0805")
      (libsource (lib "eagle-import") (part "R-US_R0805"))
    )
    (comp (ref "R14")
      (value "10k")
      (footprint "eagle-import:R0805")
      (libsource (lib "eagle-import") (part "R-US_R0805"))
    )
    (comp (ref "R21")
      (value "1M")
      (footprint "eagle-import:R0805")
      (libsource (lib "eagle-import") (part "R-US_R0805"))
    )
    (comp (ref "R27")
      (value "10k")
      (footprint "eagle-import:R0805")
      (libsource (lib "eagle-import") (part "R-US_R0805"))
    )
    (comp (ref "R36")
      (value "1k")
      (footprint "eagle-import:R0805")
      (libsource (lib "eagle-import") (part "R-US_R0805"))
    )
    (comp (ref "R39")
      (value "10k")
      (footprint "eagle-import:R0805")
      (libsource (lib "eagle-import") (part "R-US_R0805"))
    )
    (comp (ref "R40")
      (value "30k")
      (footprint "eagle-import:R0805")
      (libsource (lib "eagle-import") (part "R-US_R0805"))
    )
    (comp (ref "R41")
      (value "10k")
      (footprint "eagle-import:R0805")
      (libsource (lib "eagle-import") (part "R-US_R0805"))
    )
    (comp (ref "R42")
      (value "30k")
      (footprint "eagle-import:R0805")
      (libsource (lib "eagle-import") (part "R-US_R0805"))
    )
    (comp (ref "R43")
      (value "30k")
      (footprint "eagle-import:R0805")
      (libsource (lib "eagle-import") (part "R-US_R0805"))
    )
    (comp (ref "R44")
      (value "10k")
      (footprint "eagle-import:R0805")
      (libsource (lib "eagle-import") (part "R-US_R0805"))
    )
  )
  (nets
    (net (code "1") (name "3.3V") (class "Default")
      (node (ref "3.3V1") (pin "P$2") (pinfunction "P$2_P$2") (pintype "bidirectional"))
      (node (ref "3.3VOLTS1") (pin "1") (pinfunction "1_1") (pintype "passive"))
      (node (ref "3.3VOLTS2") (pin "1") (pinfunction "1_1") (pintype "passive"))
      (node (ref "C10") (pin "+") (pinfunction "+_+") (pintype "passive"))
      (node (ref "C32") (pin "+") (pinfunction "+_+") (pintype "passive"))
      (node (ref "C33") (pin "1") (pinfunction "1_1") (pintype "passive"))
      (node (ref "C34") (pin "1") (pinfunction "1_1") (pintype "passive"))
      (node (ref "IC5") (pin "3") (pinfunction "VO_3") (pintype "passive"))
      (node (ref "Q1") (pin "1") (pinfunction "G_1") (pintype "passive"))
      (node (ref "Q5") (pin "1") (pinfunction "G_1") (pintype "passive"))
      (node (ref "R10") (pin "2") (pinfunction "2_2") (pintype "passive"))
      (node (ref "R11") (pin "2") (pinfunction "2_2") (pintype "passive"))
      (node (ref "R12") (pin "2") (pinfunction "2_2") (pintype "passive"))
      (node (ref "R23") (pin "2") (pinfunction "2_2") (pintype "passive"))
      (node (ref "R26") (pin "2") (pinfunction "2_2") (pintype "passive"))
      (node (ref "R9") (pin "2") (pinfunction "2_2") (pintype "passive"))
      (node (ref "U$1") (pin "P$1") (pinfunction "P$1_P$1") (pintype "bidirectional"))
      (node (ref "XB1") (pin "1") (pinfunction "VCC_1") (pintype "power_in"))
    )
    (net (code "2") (name "5V") (class "Default")
      (node (ref "5V1") (pin "P$2") (pinfunction "P$2_P$2") (pintype "bidirectional"))
      (node (ref "BUZZER") (pin "+") (pinfunction "1_+") (pintype "passive"))
      (node (ref "C11") (pin "+") (pinfunction "+_+") (pintype "passive"))
      (node (ref "C28") (pin "+") (pinfunction "+_+") (pintype "passive"))
      (node (ref "C29") (pin "1") (pinfunction "1_1") (pintype "passive"))
      (node (ref "C31") (pin "1") (pinfunction "1_1") (pintype "passive"))
      (node (ref "C77") (pin "1") (pinfunction "1_1") (pintype "passive"))
      (node (ref "C81") (pin "1") (pinfunction "1_1") (pintype "passive"))
      (node (ref "D2") (pin "A") (pinfunction "A_A") (pintype "passive"))
      (node (ref "IC4") (pin "19") (pinfunction "~{RESET}_19") (pintype "input"))
      (node (ref "IC4") (pin "4") (pinfunction "VCCIO_4") (pintype "power_in"))
      (node (ref "IC7") (pin "19") (pinfunction "~{RESET}_19") (pintype "input"))
      (node (ref "IC7") (pin "4") (pinfunction "VCCIO_4") (pintype "power_in"))
      (node (ref "LED1") (pin "A") (pinfunction "A_A") (pintype "passive"))
      (node (ref "LED19") (pin "A") (pinfunction "A_A") (pintype "passive"))
      (node (ref "LED2") (pin "1") (pinfunction "GREEN_A_1") (pintype "bidirectional"))
      (node (ref "LED2") (pin "3") (pinfunction "BLUE_A_3") (pintype "bidirectional"))
      (node (ref "LED24") (pin "A") (pinfunction "A_A") (pintype "passive"))
      (node (ref "LED25") (pin "A") (pinfunction "A_A") (pintype "passive"))
      (node (ref "LED3") (pin "A") (pinfunction "A_A") (pintype "passive"))
      (node (ref "LED4") (pin "A") (pinfunction "A_A") (pintype "passive"))
      (node (ref "LED5") (pin "A") (pinfunction "A_A") (pintype "passive"))
      (node (ref "LED6") (pin "A") (pinfunction "A_A") (pintype "passive"))
      (node (ref "R22") (pin "2") (pinfunction "2_2") (pintype "passive"))
      (node (ref "R29") (pin "2") (pinfunction "2_2") (pintype "passive"))
      (node (ref "U$1") (pin "P$11") (pinfunction "P$11_P$11") (pintype "bidirectional"))
      (node (ref "U$4") (pin "P5") (pinfunction "P$5_P5") (pintype "bidirectional"))
    )
    (net (code "3") (name "GND") (class "Default")
      (node (ref "1N4742") (pin "A") (pinfunction "A_A") (pintype "passive"))
      (node (ref "3.3V1") (pin "P$1") (pinfunction "P$1_P$1") (pintype "bidirectional"))
      (node (ref "5V1") (pin "P$1") (pinfunction "P$1_P$1") (pintype "bidirectional"))
      (node (ref "ACTUATOR1") (pin "GND") (pinfunction "GND_GND") (pintype "power_in"))
      (node (ref "C1") (pin "2") (pinfunction "2_2") (pintype "passive"))
      (node (ref "C10") (pin "-") (pinfunction "-_-") (pintype "passive"))
      (node (ref "C11") (pin "-") (pinfunction "-_-") (pintype "passive"))
      (node (ref "C12") (pin "-") (pinfunction "-_-") (pintype "passive"))
      (node (ref "C13") (pin "-") (pinfunction "-_-") (pintype "passive"))
      (node (ref "C130") (pin "2") (pinfunction "2_2") (pintype "passive"))
      (node (ref "C14") (pin "2") (pinfunction "2_2") (pintype "passive"))
      (node (ref "C15") (pin "2") (pinfunction "2_2") (pintype "passive"))
      (node (ref "C16") (pin "2") (pinfunction "2_2") (pintype "passive"))
      (node (ref "C17") (pin "2") (pinfunction "2_2") (pintype "passive"))
      (node (ref "C18") (pin "2") (pinfunction "2_2") (pintype "passive"))
      (node (ref "C19") (pin "2") (pinfunction "2_2") (pintype "passive"))
      (node (ref "C2") (pin "2") (pinfunction "2_2") (pintype "passive"))
      (node (ref "C20") (pin "2") (pinfunction "2_2") (pintype "passive"))
      (node (ref "C21") (pin "2") (pinfunction "2_2") (pintype "passive"))
      (node (ref "C22") (pin "-") (pinfunction "-_-") (pintype "passive"))
      (node (ref "C23") (pin "-") (pinfunction "-_-") (pintype "passive"))
      (node (ref "C24") (pin "2") (pinfunction "2_2") (pintype "passive"))
      (node (ref "C25") (pin "2") (pinfunction "2_2") (pintype "passive"))
      (node (ref "C26") (pin "2") (pinfunction "2_2") (pintype "passive"))
      (node (ref "C27") (pin "2") (pinfunction "2_2") (pintype "passive"))
      (node (ref "C28") (pin "-") (pinfunction "-_-") (pintype "passive"))
      (node (ref "C29") (pin "2") (pinfunction "2_2") (pintype "passive"))
      (node (ref "C3") (pin "2") (pinfunction "2_2") (pintype "passive"))
      (node (ref "C30") (pin "2") (pinfunction "2_2") (pintype "passive"))
      (node (ref "C31") (pin "2") (pinfunction "2_2") (pintype "passive"))
      (node (ref "C32") (pin "-") (pinfunction "-_-") (pintype "passive"))
      (node (ref "C33") (pin "2") (pinfunction "2_2") (pintype "passive"))
      (node (ref "C34") (pin "2") (pinfunction "2_2") (pintype "passive"))
      (node (ref "C35") (pin "-") (pinfunction "-_-") (pintype "passive"))
      (node (ref "C36") (pin "2") (pinfunction "2_2") (pintype "passive"))
      (node (ref "C37") (pin "2") (pinfunction "2_2") (pintype "passive"))
      (node (ref "C4") (pin "2") (pinfunction "2_2") (pintype "passive"))
      (node (ref "C5") (pin "2") (pinfunction "2_2") (pintype "passive"))
      (node (ref "C6") (pin "2") (pinfunction "2_2") (pintype "passive"))
      (node (ref "C7") (pin "2") (pinfunction "2_2") (pintype "passive"))
      (node (ref "C74") (pin "2") (pinfunction "2_2") (pintype "passive"))
      (node (ref "C77") (pin "2") (pinfunction "2_2") (pintype "passive"))
      (node (ref "C8") (pin "-") (pinfunction "-_-") (pintype "passive"))
      (node (ref "C81") (pin "2") (pinfunction "2_2") (pintype "passive"))
      (node (ref "C9") (pin "-") (pinfunction "-_-") (pintype "passive"))
      (node (ref "CON1") (pin "4") (pinfunction "4_4") (pintype "bidirectional"))
      (node (ref "CON2") (pin "4") (pinfunction "4_4") (pintype "bidirectional"))
      (node (ref "CON3") (pin "4") (pinfunction "4_4") (pintype "bidirectional"))
      (node (ref "CON4") (pin "4") (pinfunction "4_4") (pintype "bidirectional"))
      (node (ref "CON5") (pin "4") (pinfunction "4_4") (pintype "bidirectional"))
      (node (ref "CON6") (pin "4") (pinfunction "4_4") (pintype "bidirectional"))
      (node (ref "CON7") (pin "4") (pinfunction "4_4") (pintype "bidirectional"))
      (node (ref "DTC114EET1G1-1") (pin "2") (pinfunction "E_2") (pintype "passive"))
      (node (ref "DTC114EET1G1-2") (pin "2") (pinfunction "E_2") (pintype "passive"))
      (node (ref "DTC114EET1G1-3") (pin "2") (pinfunction "E_2") (pintype "passive"))
      (node (ref "DTC114EET1G1-4") (pin "2") (pinfunction "E_2") (pintype "passive"))
      (node (ref "DTC114EET1G1-5") (pin "2") (pinfunction "E_2") (pintype "passive"))
      (node (ref "DTC114EET1G1-6") (pin "2") (pinfunction "E_2") (pintype "passive"))
      (node (ref "DTC114EET1G1-7") (pin "2") (pinfunction "E_2") (pintype "passive"))
      (node (ref "FITPC") (pin "P$2") (pinfunction "P$2_P$2") (pintype "bidirectional"))
      (node (ref "IC4") (pin "18") (pinfunction "GND_18") (pintype "power_in"))
      (node (ref "IC4") (pin "21") (pinfunction "GND_21") (pintype "power_in"))
      (node (ref "IC4") (pin "25") (pinfunction "GND_25") (pintype "power_in"))
      (node (ref "IC4") (pin "26") (pinfunction "TEST_26") (pintype "input"))
      (node (ref "IC4") (pin "7") (pinfunction "GND_7") (pintype "power_in"))
      (node (ref "IC5") (pin "2") (pinfunction "GND_2") (pintype "passive"))
      (node (ref "IC5") (pin "4") (pinfunction "GND_4") (pintype "passive"))
      (node (ref "IC7") (pin "18") (pinfunction "GND_18") (pintype "power_in"))
      (node (ref "IC7") (pin "21") (pinfunction "GND_21") (pintype "power_in"))
      (node (ref "IC7") (pin "25") (pinfunction "GND_25") (pintype "power_in"))
      (node (ref "IC7") (pin "26") (pinfunction "TEST_26") (pintype "input"))
      (node (ref "IC7") (pin "7") (pinfunction "GND_7") (pintype "power_in"))
      (node (ref "LED12") (pin "C") (pinfunction "C_C") (pintype "passive"))
      (node (ref "LED13") (pin "C") (pinfunction "C_C") (pintype "passive"))
      (node (ref "LED8") (pin "C") (pinfunction "C_C") (pintype "passive"))
      (node (ref "LED9") (pin "C") (pinfunction "C_C") (pintype "passive"))
      (node (ref "LIPO_FB") (pin "1") (pinfunction "1_1") (pintype "passive"))
      (node (ref "LIPO_INPUT") (pin "P$1") (pinfunction "1_P$1") (pintype "passive"))
      (node (ref "POWERLED4") (pin "C") (pinfunction "C_C") (pintype "passive"))
      (node (ref "Q2") (pin "2") (pinfunction "E_2") (pintype "passive"))
      (node (ref "R13") (pin "1") (pinfunction "1_1") (pintype "passive"))
      (node (ref "R21") (pin "1") (pinfunction "1_1") (pintype "passive"))
      (node (ref "R35") (pin "1") (pinfunction "1_1") (pintype "passive"))
      (node (ref "R39") (pin "2") (pinfunction "2_2") (pintype "passive"))
      (node (ref "R41") (pin "1") (pinfunction "1_1") (pintype "passive"))
      (node (ref "R44") (pin "1") (pinfunction "1_1") (pintype "passive"))
      (node (ref "RGBLED") (pin "1") (pinfunction "1_1") (pintype "passive"))
      (node (ref "TIVA1") (pin "GND") (pinfunction "GND_GND") (pintype "power_in"))
      (node (ref "U$1") (pin "P$12") (pinfunction "P$12_P$12") (pintype "bidirectional"))
      (node (ref "U$1") (pin "P$31") (pinfunction "P$31_P$31") (pintype "bidirectional"))
      (node (ref "U$4") (pin "P1") (pinfunction "P$1_P1") (pintype "bidirectional"))
      (node (ref "U1") (pin "4") (pinfunction "GND_4") (pintype "bidirectional"))
      (node (ref "U2") (pin "4") (pinfunction "GND_4") (pintype "bidirectional"))
      (node (ref "U3") (pin "4") (pinfunction "GND_4") (pintype "bidirectional"))
      (node (ref "U4") (pin "4") (pinfunction "GND_4") (pintype "bidirectional"))
      (node (ref "U5") (pin "4") (pinfunction "GND_4") (pintype "bidirectional"))
      (node (ref "U6") (pin "4") (pinfunction "GND_4") (pintype "bidirectional"))
      (node (ref "U7") (pin "4") (pinfunction "GND_4") (pintype "bidirectional"))
      (node (ref "V8ZA2P-1") (pin "P$1") (pinfunction "P$1_P$1") (pintype "bidirectional"))
      (node (ref "V8ZA2P-2") (pin "P$1") (pinfunction "P$1_P$1") (pintype "bidirectional"))
      (node (ref "V8ZA2P-3") (pin "P$2") (pinfunction "P$2_P$2") (pintype "bidirectional"))
      (node (ref "V8ZA2P-4") (pin "P$2") (pinfunction "P$2_P$2") (pintype "bidirectional"))
      (node (ref "XB1") (pin "10") (pinfunction "GND_10") (pintype "power_in"))
    )
    (net (code "4") (name "HX_RX") (class "Default")
      (node (ref "CON1") (pin "1") (pinfunction "1_1") (pintype "bidirectional"))
      (node (ref "CON2") (pin "1") (pinfunction "1_1") (pintype "bidirectional"))
      (node (ref "CON3") (pin "1") (pinfunction "1_1") (pintype "bidirectional"))
      (node (ref "CON4") (pin "1") (pinfunction "1_1") (pintype "bidirectional"))
      (node (ref "CON5") (pin "1") (pinfunction "1_1") (pintype "bidirectional"))
      (node (ref "CON6") (pin "1") (pinfunction "1_1") (pintype "bidirectional"))
      (node (ref "CON7") (pin "1") (pinfunction "1_1") (pintype "bidirectional"))
      (node (ref "IC7") (pin "1") (pinfunction "TXD_1") (pintype "output"))
      (node (ref "R45") (pin "1") (pinfunction "1_1") (pintype "passive"))
      (node (ref "RX") (pin "2") (pinfunction "2_2") (pintype "passive"))
      (node (ref "U1") (pin "5") (pinfunction "IO2_5") (pintype "bidirectional"))
      (node (ref "U2") (pin "5") (pinfunction "IO2_5") (pintype "bidirectional"))
      (node (ref "U3") (pin "5") (pinfunction "IO2_5") (pintype "bidirectional"))
      (node (ref "U4") (pin "5") (pinfunction "IO2_5") (pintype "bidirectional"))
      (node (ref "U5") (pin "5") (pinfunction "IO2_5") (pintype "bidirectional"))
      (node (ref "U6") (pin "5") (pinfunction "IO2_5") (pintype "bidirectional"))
      (node (ref "U7") (pin "5") (pinfunction "IO2_5") (pintype "bidirectional"))
      (node (ref "V8ZA2P-1") (pin "P$2") (pinfunction "P$2_P$2") (pintype "bidirectional"))
      (node (ref "V8ZA2P-3") (pin "P$1") (pinfunction "P$1_P$1") (pintype "bidirectional"))
    )
    (net (code "5") (name "HX_TX") (class "Default")
      (node (ref "CON1") (pin "2") (pinfunction "2_2") (pintype "bidirectional"))
      (node (ref "CON2") (pin "2") (pinfunction "2_2") (pintype "bidirectional"))
      (node (ref "CON3") (pin "2") (pinfunction "2_2") (pintype "bidirectional"))
      (node (ref "CON4") (pin "2") (pinfunction "2_2") (pintype "bidirectional"))
      (node (ref "CON5") (pin "2") (pinfunction "2_2") (pintype "bidirectional"))
      (node (ref "CON6") (pin "2") (pinfunction "2_2") (pintype "bidirectional"))
      (node (ref "CON7") (pin "2") (pinfunction "2_2") (pintype "bidirectional"))
      (node (ref "IC7") (pin "5") (pinfunction "RXD_5") (pintype "input"))
      (node (ref "R46") (pin "1") (pinfunction "1_1") (pintype "passive"))
      (node (ref "TX") (pin "2") (pinfunction "2_2") (pintype "passive"))
      (node (ref "U1") (pin "3") (pinfunction "IO1_3") (pintype "input"))
      (node (ref "U2") (pin "3") (pinfunction "IO1_3") (pintype "input"))
      (node (ref "U3") (pin "3") (pinfunction "IO1_3") (pintype "input"))
      (node (ref "U4") (pin "3") (pinfunction "IO1_3") (pintype "input"))
      (node (ref "U5") (pin "3") (pinfunction "IO1_3") (pintype "input"))
      (node (ref "U6") (pin "3") (pinfunction "IO1_3") (pintype "input"))
      (node (ref "U7") (pin "3") (pinfunction "IO1_3") (pintype "input"))
      (node (ref "V8ZA2P-2") (pin "P$2") (pinfunction "P$2_P$2") (pintype "bidirectional"))
      (node (ref "V8ZA2P-4") (pin "P$1") (pinfunction "P$1_P$1") (pintype "bidirectional"))
    )
    (net (code "6") (name "MOSFET_CTRL1") (class "Default")
      (node (ref "10A") (pin "1") (pinfunction "1_1") (pintype "passive"))
      (node (ref "CSD8503KCS") (pin "3") (pinfunction "S_3") (pintype "passive"))
    )
    (net (code "7") (name "MOSFET_CTRL2") (class "Default")
      (node (ref "CSD8503KCS1") (pin "3") (pinfunction "S_3") (pintype "passive"))
      (node (ref "PTCFUSE1") (pin "1") (pinfunction "1_1") (pintype "passive"))
    )
    (net (code "8") (name "Net-(10A-Pad2)") (class "Default")
      (node (ref "10A") (pin "2") (pinfunction "2_2") (pintype "passive"))
      (node (ref "C16") (pin "1") (pinfunction "1_1") (pintype "passive"))
      (node (ref "C35") (pin "+") (pinfunction "+_+") (pintype "passive"))
      (node (ref "C36") (pin "1") (pinfunction "1_1") (pintype "passive"))
      (node (ref "C37") (pin "1") (pinfunction "1_1") (pintype "passive"))
      (node (ref "FITPC") (pin "P$1") (pinfunction "P$1_P$1") (pintype "bidirectional"))
    )
    (net (code "9") (name "Net-(20A-Pad2)") (class "Default")
      (node (ref "20A") (pin "2") (pinfunction "2_2") (pintype "passive"))
      (node (ref "MAIN_PWR_SW") (pin "1") (pinfunction "1_1") (pintype "passive"))
    )
    (net (code "10") (name "Net-(ACTUATOR1-PadVBUS)") (class "Default")
      (node (ref "ACTUATOR1") (pin "VBUS") (pinfunction "VBUS_VBUS") (pintype "power_in"))
      (node (ref "C74") (pin "1") (pinfunction "1_1") (pintype "passive"))
      (node (ref "L2") (pin "1") (pinfunction "1_1") (pintype "passive"))
    )
    (net (code "11") (name "Net-(BUZZER-2)") (class "Default")
      (node (ref "BUZZER") (pin "-") (pinfunction "2_-") (pintype "passive"))
      (node (ref "Q2") (pin "3") (pinfunction "C_3") (pintype "passive"))
    )
    (net (code "12") (name "Net-(C1-Pad1)") (class "Default")
      (node (ref "C1") (pin "1") (pinfunction "1_1") (pintype "passive"))
      (node (ref "C12") (pin "+") (pinfunction "+_+") (pintype "passive"))
      (node (ref "C13") (pin "+") (pinfunction "+_+") (pintype "passive"))
      (node (ref "C17") (pin "1") (pinfunction "1_1") (pintype "passive"))
      (node (ref "C18") (pin "1") (pinfunction "1_1") (pintype "passive"))
      (node (ref "C19") (pin "1") (pinfunction "1_1") (pintype "passive"))
      (node (ref "C2") (pin "1") (pinfunction "1_1") (pintype "passive"))
      (node (ref "C20") (pin "1") (pinfunction "1_1") (pintype "passive"))
      (node (ref "C21") (pin "1") (pinfunction "1_1") (pintype "passive"))
      (node (ref "CON1") (pin "3") (pinfunction "3_3") (pintype "bidirectional"))
      (node (ref "CON2") (pin "3") (pinfunction "3_3") (pintype "bidirectional"))
      (node (ref "CON3") (pin "3") (pinfunction "3_3") (pintype "bidirectional"))
      (node (ref "CON4") (pin "3") (pinfunction "3_3") (pintype "bidirectional"))
      (node (ref "CON5") (pin "3") (pinfunction "3_3") (pintype "bidirectional"))
      (node (ref "CON6") (pin "3") (pinfunction "3_3") (pintype "bidirectional"))
      (node (ref "CON7") (pin "3") (pinfunction "3_3") (pintype "bidirectional"))
      (node (ref "F2") (pin "1") (pinfunction "1_1") (pintype "passive"))
    )
    (net (code "13") (name "Net-(C30-Pad1)") (class "Default")
      (node (ref "C30") (pin "1") (pinfunction "1_1") (pintype "passive"))
      (node (ref "L1") (pin "1") (pinfunction "1_1") (pintype "passive"))
      (node (ref "TIVA1") (pin "VBUS") (pinfunction "VBUS_VBUS") (pintype "power_in"))
    )
    (net (code "14") (name "Net-(C130-Pad1)") (class "Default")
      (node (ref "C130") (pin "1") (pinfunction "1_1") (pintype "passive"))
      (node (ref "R14") (pin "2") (pinfunction "2_2") (pintype "passive"))
      (node (ref "R39") (pin "1") (pinfunction "1_1") (pintype "passive"))
    )
    (net (code "15") (name "Net-(DTC114EET1G1-1-B)") (class "Default")
      (node (ref "DTC114EET1G1-1") (pin "1") (pinfunction "B_1") (pintype "passive"))
      (node (ref "R31") (pin "2") (pinfunction "2_2") (pintype "passive"))
    )
    (net (code "16") (name "Net-(DTC114EET1G1-1-C)") (class "Default")
      (node (ref "DTC114EET1G1-1") (pin "3") (pinfunction "C_3") (pintype "passive"))
      (node (ref "R24") (pin "2") (pinfunction "2_2") (pintype "passive"))
    )
    (net (code "17") (name "Net-(DTC114EET1G1-2-B)") (class "Default")
      (node (ref "DTC114EET1G1-2") (pin "1") (pinfunction "B_1") (pintype "passive"))
      (node (ref "R32") (pin "2") (pinfunction "2_2") (pintype "passive"))
    )
    (net (code "18") (name "Net-(DTC114EET1G1-2-C)") (class "Default")
      (node (ref "DTC114EET1G1-2") (pin "3") (pinfunction "C_3") (pintype "passive"))
      (node (ref "R25") (pin "1") (pinfunction "1_1") (pintype "passive"))
    )
    (net (code "19") (name "Net-(DTC114EET1G1-3-B)") (class "Default")
      (node (ref "DTC114EET1G1-3") (pin "1") (pinfunction "B_1") (pintype "passive"))
      (node (ref "R33") (pin "2") (pinfunction "2_2") (pintype "passive"))
    )
    (net (code "20") (name "Net-(DTC114EET1G1-3-C)") (class "Default")
      (node (ref "DTC114EET1G1-3") (pin "3") (pinfunction "C_3") (pintype "passive"))
      (node (ref "R30") (pin "1") (pinfunction "1_1") (pintype "passive"))
    )
    (net (code "21") (name "Net-(DTC114EET1G1-4-B)") (class "Default")
      (node (ref "DTC114EET1G1-4") (pin "1") (pinfunction "B_1") (pintype "passive"))
      (node (ref "R1") (pin "2") (pinfunction "2_2") (pintype "passive"))
    )
    (net (code "22") (name "Net-(DTC114EET1G1-4-C)") (class "Default")
      (node (ref "DTC114EET1G1-4") (pin "3") (pinfunction "C_3") (pintype "passive"))
      (node (ref "R17") (pin "1") (pinfunction "1_1") (pintype "passive"))
    )
    (net (code "23") (name "Net-(DTC114EET1G1-5-B)") (class "Default")
      (node (ref "DTC114EET1G1-5") (pin "1") (pinfunction "B_1") (pintype "passive"))
      (node (ref "R3") (pin "2") (pinfunction "2_2") (pintype "passive"))
    )
    (net (code "24") (name "Net-(DTC114EET1G1-5-C)") (class "Default")
      (node (ref "DTC114EET1G1-5") (pin "3") (pinfunction "C_3") (pintype "passive"))
      (node (ref "R2") (pin "1") (pinfunction "1_1") (pintype "passive"))
    )
    (net (code "25") (name "Net-(DTC114EET1G1-6-B)") (class "Default")
      (node (ref "DTC114EET1G1-6") (pin "1") (pinfunction "B_1") (pintype "passive"))
      (node (ref "R5") (pin "2") (pinfunction "2_2") (pintype "passive"))
    )
    (net (code "26") (name "Net-(DTC114EET1G1-6-C)") (class "Default")
      (node (ref "DTC114EET1G1-6") (pin "3") (pinfunction "C_3") (pintype "passive"))
      (node (ref "R4") (pin "1") (pinfunction "1_1") (pintype "passive"))
    )
    (net (code "27") (name "Net-(DTC114EET1G1-7-B)") (class "Default")
      (node (ref "DTC114EET1G1-7") (pin "1") (pinfunction "B_1") (pintype "passive"))
      (node (ref "R7") (pin "2") (pinfunction "2_2") (pintype "passive"))
    )
    (net (code "28") (name "Net-(DTC114EET1G1-7-C)") (class "Default")
      (node (ref "DTC114EET1G1-7") (pin "3") (pinfunction "C_3") (pintype "passive"))
      (node (ref "R6") (pin "1") (pinfunction "1_1") (pintype "passive"))
    )
    (net (code "29") (name "Net-(F2-Pad2)") (class "Default")
      (node (ref "F2") (pin "2") (pinfunction "2_2") (pintype "passive"))
      (node (ref "PTCFUSE1") (pin "2") (pinfunction "2_2") (pintype "passive"))
    )
    (net (code "30") (name "Net-(IC4-3V3OUT)") (class "Default")
      (node (ref "C26") (pin "1") (pinfunction "1_1") (pintype "passive"))
      (node (ref "IC4") (pin "17") (pinfunction "3V3OUT_17") (pintype "output"))
    )
    (net (code "31") (name "Net-(IC4-CBUS0)") (class "Default")
      (node (ref "IC4") (pin "23") (pinfunction "CBUS0_23") (pintype "bidirectional"))
      (node (ref "R37") (pin "2") (pinfunction "2_2") (pintype "passive"))
    )
    (net (code "32") (name "Net-(IC4-CBUS1)") (class "Default")
      (node (ref "IC4") (pin "22") (pinfunction "CBUS1_22") (pintype "bidirectional"))
      (node (ref "R38") (pin "2") (pinfunction "2_2") (pintype "passive"))
    )
    (net (code "33") (name "Net-(IC4-USBDM)") (class "Default")
      (node (ref "IC4") (pin "16") (pinfunction "USBDM_16") (pintype "bidirectional"))
      (node (ref "TIVA1") (pin "D-") (pinfunction "D-_D-") (pintype "bidirectional"))
    )
    (net (code "34") (name "Net-(IC4-USBDP)") (class "Default")
      (node (ref "IC4") (pin "15") (pinfunction "USBDP_15") (pintype "bidirectional"))
      (node (ref "TIVA1") (pin "D+") (pinfunction "D+_D+") (pintype "bidirectional"))
    )
    (net (code "35") (name "Net-(IC4-VCC)") (class "Default")
      (node (ref "C23") (pin "+") (pinfunction "+_+") (pintype "passive"))
      (node (ref "C25") (pin "1") (pinfunction "1_1") (pintype "passive"))
      (node (ref "IC4") (pin "20") (pinfunction "VCC_20") (pintype "power_in"))
      (node (ref "L1") (pin "2") (pinfunction "2_2") (pintype "passive"))
    )
    (net (code "36") (name "Net-(IC4-~{DTR})") (class "Default")
      (node (ref "IC4") (pin "2") (pinfunction "~{DTR}_2") (pintype "output"))
      (node (ref "RST_FTDI_TIVA1") (pin "2") (pinfunction "2_2") (pintype "passive"))
    )
    (net (code "37") (name "Net-(IC5-VIN)") (class "Default")
      (node (ref "C8") (pin "+") (pinfunction "+_+") (pintype "passive"))
      (node (ref "D2") (pin "C") (pinfunction "C_C") (pintype "passive"))
      (node (ref "IC5") (pin "1") (pinfunction "VIN_1") (pintype "input"))
    )
    (net (code "38") (name "Net-(IC7-3V3OUT)") (class "Default")
      (node (ref "C27") (pin "1") (pinfunction "1_1") (pintype "passive"))
      (node (ref "IC7") (pin "17") (pinfunction "3V3OUT_17") (pintype "output"))
    )
    (net (code "39") (name "Net-(IC7-CBUS0)") (class "Default")
      (node (ref "IC7") (pin "23") (pinfunction "CBUS0_23") (pintype "bidirectional"))
      (node (ref "R47") (pin "2") (pinfunction "2_2") (pintype "passive"))
    )
    (net (code "40") (name "Net-(IC7-CBUS1)") (class "Default")
      (node (ref "IC7") (pin "22") (pinfunction "CBUS1_22") (pintype "bidirectional"))
      (node (ref "R48") (pin "2") (pinfunction "2_2") (pintype "passive"))
    )
    (net (code "41") (name "Net-(IC7-USBDM)") (class "Default")
      (node (ref "ACTUATOR1") (pin "D-") (pinfunction "D-_D-") (pintype "bidirectional"))
      (node (ref "IC7") (pin "16") (pinfunction "USBDM_16") (pintype "bidirectional"))
    )
    (net (code "42") (name "Net-(IC7-USBDP)") (class "Default")
      (node (ref "ACTUATOR1") (pin "D+") (pinfunction "D+_D+") (pintype "bidirectional"))
      (node (ref "IC7") (pin "15") (pinfunction "USBDP_15") (pintype "bidirectional"))
    )
    (net (code "43") (name "Net-(IC7-VCC)") (class "Default")
      (node (ref "C22") (pin "+") (pinfunction "+_+") (pintype "passive"))
      (node (ref "C24") (pin "1") (pinfunction "1_1") (pintype "passive"))
      (node (ref "IC7") (pin "20") (pinfunction "VCC_20") (pintype "power_in"))
      (node (ref "L2") (pin "2") (pinfunction "2_2") (pintype "passive"))
    )
    (net (code "44") (name "Net-(IC7-~{DTR})") (class "Default")
      (node (ref "IC7") (pin "2") (pinfunction "~{DTR}_2") (pintype "output"))
      (node (ref "RST_ACTUATOR1") (pin "2") (pinfunction "2_2") (pintype "passive"))
    )
    (net (code "45") (name "Net-(LED1-PadC)") (class "Default")
      (node (ref "LED1") (pin "C") (pinfunction "C_C") (pintype "passive"))
      (node (ref "R2") (pin "2") (pinfunction "2_2") (pintype "passive"))
    )
    (net (code "46") (name "Net-(LED2-BLUE_C)") (class "Default")
      (node (ref "LED2") (pin "4") (pinfunction "BLUE_C_4") (pintype "bidirectional"))
      (node (ref "R30") (pin "2") (pinfunction "2_2") (pintype "passive"))
      (node (ref "RGBLED") (pin "2") (pinfunction "1_2") (pintype "passive"))
    )
    (net (code "47") (name "Net-(LED2-GREEN_C)") (class "Default")
      (node (ref "LED2") (pin "6") (pinfunction "GREEN_C_6") (pintype "bidirectional"))
      (node (ref "R25") (pin "2") (pinfunction "2_2") (pintype "passive"))
      (node (ref "RGBLED") (pin "3") (pinfunction "1_3") (pintype "passive"))
    )
    (net (code "48") (name "Net-(LED2-RED_C)") (class "Default")
      (node (ref "LED2") (pin "5") (pinfunction "RED_C_5") (pintype "bidirectional"))
      (node (ref "R24") (pin "1") (pinfunction "1_1") (pintype "passive"))
      (node (ref "RGBLED") (pin "4") (pinfunction "1_4") (pintype "passive"))
    )
    (net (code "49") (name "Net-(LED3-PadC)") (class "Default")
      (node (ref "LED3") (pin "C") (pinfunction "C_C") (pintype "passive"))
      (node (ref "R37") (pin "1") (pinfunction "1_1") (pintype "passive"))
    )
    (net (code "50") (name "Net-(LED4-PadC)") (class "Default")
      (node (ref "LED4") (pin "C") (pinfunction "C_C") (pintype "passive"))
      (node (ref "R38") (pin "1") (pinfunction "1_1") (pintype "passive"))
    )
    (net (code "51") (name "Net-(LED5-PadC)") (class "Default")
      (node (ref "LED5") (pin "C") (pinfunction "C_C") (pintype "passive"))
      (node (ref "R4") (pin "2") (pinfunction "2_2") (pintype "passive"))
    )
    (net (code "52") (name "Net-(LED6-PadC)") (class "Default")
      (node (ref "LED6") (pin "C") (pinfunction "C_C") (pintype "passive"))
      (node (ref "R6") (pin "2") (pinfunction "2_2") (pintype "passive"))
    )
    (net (code "53") (name "Net-(LED8-PadA)") (class "Default")
      (node (ref "LED8") (pin "A") (pinfunction "A_A") (pintype "passive"))
      (node (ref "R15") (pin "1") (pinfunction "1_1") (pintype "passive"))
    )
    (net (code "54") (name "Net-(LED9-PadA)") (class "Default")
      (node (ref "LED9") (pin "A") (pinfunction "A_A") (pintype "passive"))
      (node (ref "R16") (pin "1") (pinfunction "1_1") (pintype "passive"))
    )
    (net (code "55") (name "Net-(LED12-PadA)") (class "Default")
      (node (ref "LED12") (pin "A") (pinfunction "A_A") (pintype "passive"))
      (node (ref "R45") (pin "2") (pinfunction "2_2") (pintype "passive"))
    )
    (net (code "56") (name "Net-(LED13-PadA)") (class "Default")
      (node (ref "LED13") (pin "A") (pinfunction "A_A") (pintype "passive"))
      (node (ref "R46") (pin "2") (pinfunction "2_2") (pintype "passive"))
    )
    (net (code "57") (name "Net-(LED19-PadC)") (class "Default")
      (node (ref "LED19") (pin "C") (pinfunction "C_C") (pintype "passive"))
      (node (ref "R17") (pin "2") (pinfunction "2_2") (pintype "passive"))
    )
    (net (code "58") (name "Net-(LED24-PadC)") (class "Default")
      (node (ref "LED24") (pin "C") (pinfunction "C_C") (pintype "passive"))
      (node (ref "R47") (pin "1") (pinfunction "1_1") (pintype "passive"))
    )
    (net (code "59") (name "Net-(LED25-PadC)") (class "Default")
      (node (ref "LED25") (pin "C") (pinfunction "C_C") (pintype "passive"))
      (node (ref "R48") (pin "1") (pinfunction "1_1") (pintype "passive"))
    )
    (net (code "60") (name "Net-(LIPO_FB-Pad3)") (class "Default")
      (node (ref "LIPO_FB") (pin "3") (pinfunction "3_3") (pintype "passive"))
      (node (ref "R40") (pin "2") (pinfunction "2_2") (pintype "passive"))
    )
    (net (code "61") (name "Net-(LIPO_FB-Pad4)") (class "Default")
      (node (ref "LIPO_FB") (pin "4") (pinfunction "4_4") (pintype "passive"))
      (node (ref "R42") (pin "2") (pinfunction "2_2") (pintype "passive"))
    )
    (net (code "62") (name "Net-(LIPO_INPUT-2)") (class "Default")
      (node (ref "20A") (pin "1") (pinfunction "1_1") (pintype "passive"))
      (node (ref "LIPO_INPUT") (pin "P$2") (pinfunction "2_P$2") (pintype "passive"))
    )
    (net (code "63") (name "Net-(POWERLED4-PadA)") (class "Default")
      (node (ref "POWERLED4") (pin "A") (pinfunction "A_A") (pintype "passive"))
      (node (ref "R36") (pin "1") (pinfunction "1_1") (pintype "passive"))
    )
    (net (code "64") (name "Net-(Q2-B)") (class "Default")
      (node (ref "Q2") (pin "1") (pinfunction "B_1") (pintype "passive"))
      (node (ref "R28") (pin "1") (pinfunction "1_1") (pintype "passive"))
    )
    (net (code "65") (name "Net-(R27-Pad2)") (class "Default")
      (node (ref "R27") (pin "2") (pinfunction "2_2") (pintype "passive"))
      (node (ref "R43") (pin "1") (pinfunction "1_1") (pintype "passive"))
    )
    (net (code "66") (name "Net-(R42-Pad1)") (class "Default")
      (node (ref "R42") (pin "1") (pinfunction "1_1") (pintype "passive"))
      (node (ref "R43") (pin "2") (pinfunction "2_2") (pintype "passive"))
    )
    (net (code "67") (name "Net-(U$4-P$4)") (class "Default")
      (node (ref "R35") (pin "2") (pinfunction "2_2") (pintype "passive"))
      (node (ref "U$4") (pin "P4") (pinfunction "P$4_P4") (pintype "bidirectional"))
    )
    (net (code "68") (name "Net-(XB1-ASSOC{slash}AD5{slash}DIO5)") (class "Default")
      (node (ref "R15") (pin "2") (pinfunction "2_2") (pintype "passive"))
      (node (ref "XB1") (pin "15") (pinfunction "ASSOC/AD5/DIO5_15") (pintype "bidirectional"))
    )
    (net (code "69") (name "Net-(XB1-PWM0{slash}RSSI)") (class "Default")
      (node (ref "R16") (pin "2") (pinfunction "2_2") (pintype "passive"))
      (node (ref "XB1") (pin "6") (pinfunction "PWM0/RSSI_6") (pintype "output"))
    )
    (net (code "70") (name "P2") (class "Default")
      (node (ref "FORCE_LEFT") (pin "1") (pinfunction "1_1") (pintype "passive"))
      (node (ref "U$1") (pin "P$2") (pinfunction "P$2_P$2") (pintype "bidirectional"))
    )
    (net (code "71") (name "P3") (class "Default")
      (node (ref "IC4") (pin "1") (pinfunction "TXD_1") (pintype "output"))
      (node (ref "U$1") (pin "P$3") (pinfunction "P$3_P$3") (pintype "bidirectional"))
    )
    (net (code "72") (name "P4") (class "Default")
      (node (ref "IC4") (pin "5") (pinfunction "RXD_5") (pintype "input"))
      (node (ref "U$1") (pin "P$4") (pinfunction "P$4_P$4") (pintype "bidirectional"))
    )
    (net (code "73") (name "P5") (class "Default")
      (node (ref "C14") (pin "1") (pinfunction "1_1") (pintype "passive"))
      (node (ref "R27") (pin "1") (pinfunction "1_1") (pintype "passive"))
      (node (ref "R44") (pin "2") (pinfunction "2_2") (pintype "passive"))
      (node (ref "U$1") (pin "P$5") (pinfunction "P$5_P$5") (pintype "bidirectional"))
    )
    (net (code "74") (name "P6") (class "Default")
      (node (ref "C15") (pin "1") (pinfunction "1_1") (pintype "passive"))
      (node (ref "R40") (pin "1") (pinfunction "1_1") (pintype "passive"))
      (node (ref "R41") (pin "2") (pinfunction "2_2") (pintype "passive"))
      (node (ref "U$1") (pin "P$6") (pinfunction "P$6_P$6") (pintype "bidirectional"))
    )
    (net (code "75") (name "P7") (class "Default")
      (node (ref "LIPO_FB") (pin "2") (pinfunction "2_2") (pintype "passive"))
      (node (ref "R14") (pin "1") (pinfunction "1_1") (pintype "passive"))
      (node (ref "U$1") (pin "P$7") (pinfunction "P$7_P$7") (pintype "bidirectional"))
    )
    (net (code "76") (name "P8") (class "Default")
      (node (ref "LED") (pin "4") (pinfunction "1_4") (pintype "passive"))
      (node (ref "R3") (pin "1") (pinfunction "1_1") (pintype "passive"))
      (node (ref "U$1") (pin "P$8") (pinfunction "P$8_P$8") (pintype "bidirectional"))
    )
    (net (code "77") (name "P9") (class "Default")
      (node (ref "LED") (pin "3") (pinfunction "1_3") (pintype "passive"))
      (node (ref "R1") (pin "1") (pinfunction "1_1") (pintype "passive"))
      (node (ref "U$1") (pin "P$9") (pinfunction "P$9_P$9") (pintype "bidirectional"))
    )
    (net (code "78") (name "P10") (class "Default")
      (node (ref "LED") (pin "2") (pinfunction "1_2") (pintype "passive"))
      (node (ref "R7") (pin "1") (pinfunction "1_1") (pintype "passive"))
      (node (ref "U$1") (pin "P$10") (pinfunction "P$10_P$10") (pintype "bidirectional"))
    )
    (net (code "79") (name "P13") (class "Default")
      (node (ref "FORCE_LEFT") (pin "2") (pinfunction "1_2") (pintype "passive"))
      (node (ref "U$1") (pin "P$13") (pinfunction "P$13_P$13") (pintype "bidirectional"))
    )
    (net (code "80") (name "P14") (class "Default")
      (node (ref "FORCE_LEFT") (pin "3") (pinfunction "1_3") (pintype "passive"))
      (node (ref "U$1") (pin "P$14") (pinfunction "P$14_P$14") (pintype "bidirectional"))
    )
    (net (code "81") (name "P15") (class "Default")
      (node (ref "FORCE_LEFT") (pin "4") (pinfunction "1_4") (pintype "passive"))
      (node (ref "U$1") (pin "P$15") (pinfunction "P$15_P$15") (pintype "bidirectional"))
    )
    (net (code "82") (name "P16") (class "Default")
      (node (ref "FORCE_RIGHT") (pin "1") (pinfunction "1_1") (pintype "passive"))
      (node (ref "U$1") (pin "P$16") (pinfunction "P$16_P$16") (pintype "bidirectional"))
    )
    (net (code "83") (name "P17") (class "Default")
      (node (ref "FORCE_RIGHT") (pin "2") (pinfunction "1_2") (pintype "passive"))
      (node (ref "U$1") (pin "P$17") (pinfunction "P$17_P$17") (pintype "bidirectional"))
    )
    (net (code "84") (name "P18") (class "Default")
      (node (ref "FORCE_RIGHT") (pin "3") (pinfunction "1_3") (pintype "passive"))
      (node (ref "U$1") (pin "P$18") (pinfunction "P$18_P$18") (pintype "bidirectional"))
    )
    (net (code "85") (name "P19") (class "Default")
      (node (ref "FORCE_RIGHT") (pin "4") (pinfunction "1_4") (pintype "passive"))
      (node (ref "U$1") (pin "P$19") (pinfunction "P$19_P$19") (pintype "bidirectional"))
    )
    (net (code "86") (name "P20") (class "Default")
      (node (ref "LED") (pin "1") (pinfunction "1_1") (pintype "passive"))
      (node (ref "R5") (pin "1") (pinfunction "1_1") (pintype "passive"))
      (node (ref "U$1") (pin "P$20") (pinfunction "P$20_P$20") (pintype "bidirectional"))
    )
    (net (code "87") (name "P21") (class "Default")
      (node (ref "CSD8503KCS") (pin "1") (pinfunction "G_1") (pintype "passive"))
      (node (ref "R21") (pin "2") (pinfunction "2_2") (pintype "passive"))
      (node (ref "U$1") (pin "P$21") (pinfunction "P$21_P$21") (pintype "bidirectional"))
    )
    (net (code "88") (name "P22") (class "Default")
      (node (ref "PIN22") (pin "1") (pinfunction "1_1") (pintype "passive"))
      (node (ref "U$1") (pin "P$22") (pinfunction "P$22_P$22") (pintype "bidirectional"))
    )
    (net (code "89") (name "P23") (class "Default")
      (node (ref "R28") (pin "2") (pinfunction "2_2") (pintype "passive"))
      (node (ref "U$1") (pin "P$23") (pinfunction "P$23_P$23") (pintype "bidirectional"))
    )
    (net (code "90") (name "P24") (class "Default")
      (node (ref "Q1") (pin "2") (pinfunction "S_2") (pintype "passive"))
      (node (ref "R23") (pin "1") (pinfunction "1_1") (pintype "passive"))
      (node (ref "U$1") (pin "P$24") (pinfunction "P$24_P$24") (pintype "bidirectional"))
    )
    (net (code "91") (name "P25") (class "Default")
      (node (ref "Q5") (pin "3") (pinfunction "D_3") (pintype "passive"))
      (node (ref "R26") (pin "1") (pinfunction "1_1") (pintype "passive"))
      (node (ref "U$1") (pin "P$25") (pinfunction "P$25_P$25") (pintype "bidirectional"))
    )
    (net (code "92") (name "P28") (class "Default")
      (node (ref "C6") (pin "1") (pinfunction "1_1") (pintype "passive"))
      (node (ref "R11") (pin "1") (pinfunction "1_1") (pintype "passive"))
      (node (ref "SW1") (pin "3") (pinfunction "1_3") (pintype "passive"))
      (node (ref "U$1") (pin "P$28") (pinfunction "P$28_P$28") (pintype "bidirectional"))
    )
    (net (code "93") (name "P29") (class "Default")
      (node (ref "C4") (pin "1") (pinfunction "1_1") (pintype "passive"))
      (node (ref "R10") (pin "1") (pinfunction "1_1") (pintype "passive"))
      (node (ref "SW1") (pin "2") (pinfunction "1_2") (pintype "passive"))
      (node (ref "U$1") (pin "P$29") (pinfunction "P$29_P$29") (pintype "bidirectional"))
    )
    (net (code "94") (name "P30") (class "Default")
      (node (ref "C5") (pin "1") (pinfunction "1_1") (pintype "passive"))
      (node (ref "R9") (pin "1") (pinfunction "1_1") (pintype "passive"))
      (node (ref "SW1") (pin "1") (pinfunction "1_1") (pintype "passive"))
      (node (ref "U$1") (pin "P$30") (pinfunction "P$30_P$30") (pintype "bidirectional"))
    )
    (net (code "95") (name "P33") (class "Default")
      (node (ref "CSD8503KCS1") (pin "1") (pinfunction "G_1") (pintype "passive"))
      (node (ref "R13") (pin "2") (pinfunction "2_2") (pintype "passive"))
      (node (ref "U$1") (pin "P$33") (pinfunction "P$33_P$33") (pintype "bidirectional"))
    )
    (net (code "96") (name "P34") (class "Default")
      (node (ref "C7") (pin "1") (pinfunction "1_1") (pintype "passive"))
      (node (ref "R12") (pin "1") (pinfunction "1_1") (pintype "passive"))
      (node (ref "SW1") (pin "4") (pinfunction "1_4") (pintype "passive"))
      (node (ref "U$1") (pin "P$34") (pinfunction "P$34_P$34") (pintype "bidirectional"))
    )
    (net (code "97") (name "P35") (class "Default")
      (node (ref "RST_ACTUATOR1") (pin "1") (pinfunction "1_1") (pintype "passive"))
      (node (ref "RST_FTDI_TIVA1") (pin "1") (pinfunction "1_1") (pintype "passive"))
      (node (ref "U$1") (pin "P$35") (pinfunction "P$35_P$35") (pintype "bidirectional"))
    )
    (net (code "98") (name "P38") (class "Default")
      (node (ref "R31") (pin "1") (pinfunction "1_1") (pintype "passive"))
      (node (ref "U$1") (pin "P$38") (pinfunction "P$38_P$38") (pintype "bidirectional"))
    )
    (net (code "99") (name "P39") (class "Default")
      (node (ref "R32") (pin "1") (pinfunction "1_1") (pintype "passive"))
      (node (ref "U$1") (pin "P$39") (pinfunction "P$39_P$39") (pintype "bidirectional"))
    )
    (net (code "100") (name "P40") (class "Default")
      (node (ref "R33") (pin "1") (pinfunction "1_1") (pintype "passive"))
      (node (ref "U$1") (pin "P$40") (pinfunction "P$40_P$40") (pintype "bidirectional"))
    )
    (net (code "101") (name "RX3") (class "Default")
      (node (ref "U$1") (pin "P$26") (pinfunction "P$26_P$26") (pintype "bidirectional"))
      (node (ref "XB1") (pin "2") (pinfunction "DOUT_2") (pintype "output"))
    )
    (net (code "102") (name "TIVA_RX") (class "Default")
      (node (ref "Q1") (pin "3") (pinfunction "D_3") (pintype "passive"))
      (node (ref "R22") (pin "1") (pinfunction "1_1") (pintype "passive"))
      (node (ref "TX") (pin "1") (pinfunction "1_1") (pintype "passive"))
    )
    (net (code "103") (name "TIVA_TX") (class "Default")
      (node (ref "Q5") (pin "2") (pinfunction "S_2") (pintype "passive"))
      (node (ref "R29") (pin "1") (pinfunction "1_1") (pintype "passive"))
      (node (ref "RX") (pin "1") (pinfunction "1_1") (pintype "passive"))
    )
    (net (code "104") (name "TX3") (class "Default")
      (node (ref "U$1") (pin "P$27") (pinfunction "P$27_P$27") (pintype "bidirectional"))
      (node (ref "XB1") (pin "3") (pinfunction "DIN/~{CONFIG}_3") (pintype "input"))
    )
    (net (code "105") (name "VCC") (class "Default")
      (node (ref "1N4742") (pin "C") (pinfunction "C_C") (pintype "passive"))
      (node (ref "C3") (pin "1") (pinfunction "1_1") (pintype "passive"))
      (node (ref "C9") (pin "+") (pinfunction "+_+") (pintype "passive"))
      (node (ref "CSD8503KCS") (pin "2") (pinfunction "D_2") (pintype "passive"))
      (node (ref "CSD8503KCS1") (pin "2") (pinfunction "D_2") (pintype "passive"))
      (node (ref "MAIN_PWR_SW") (pin "2") (pinfunction "2_2") (pintype "passive"))
      (node (ref "R36") (pin "2") (pinfunction "2_2") (pintype "passive"))
      (node (ref "U$4") (pin "P2") (pinfunction "P$2_P2") (pintype "bidirectional"))
    )
    (net (code "106") (name "unconnected-(ACTUATOR1-PadID)") (class "Default")
      (node (ref "ACTUATOR1") (pin "ID") (pinfunction "ID_ID") (pintype "bidirectional"))
    )
    (net (code "107") (name "unconnected-(IC4-CBUS2-Pad13)") (class "Default")
      (node (ref "IC4") (pin "13") (pinfunction "CBUS2_13") (pintype "bidirectional"))
    )
    (net (code "108") (name "unconnected-(IC4-CBUS3-Pad14)") (class "Default")
      (node (ref "IC4") (pin "14") (pinfunction "CBUS3_14") (pintype "bidirectional"))
    )
    (net (code "109") (name "unconnected-(IC4-CBUS4-Pad12)") (class "Default")
      (node (ref "IC4") (pin "12") (pinfunction "CBUS4_12") (pintype "bidirectional"))
    )
    (net (code "110") (name "unconnected-(IC4-OSCI-Pad27)") (class "Default")
      (node (ref "IC4") (pin "27") (pinfunction "OSCI_27") (pintype "input"))
    )
    (net (code "111") (name "unconnected-(IC4-OSCO-Pad28)") (class "Default")
      (node (ref "IC4") (pin "28") (pinfunction "OSCO_28") (pintype "output"))
    )
    (net (code "112") (name "unconnected-(IC4-~{CTS}-Pad11)") (class "Default")
      (node (ref "IC4") (pin "11") (pinfunction "~{CTS}_11") (pintype "input"))
    )
    (net (code "113") (name "unconnected-(IC4-~{DCD}-Pad10)") (class "Default")
      (node (ref "IC4") (pin "10") (pinfunction "~{DCD}_10") (pintype "input"))
    )
    (net (code "114") (name "unconnected-(IC4-~{DSR}-Pad9)") (class "Default")
      (node (ref "IC4") (pin "9") (pinfunction "~{DSR}_9") (pintype "input"))
    )
    (net (code "115") (name "unconnected-(IC4-~{RI}-Pad6)") (class "Default")
      (node (ref "IC4") (pin "6") (pinfunction "~{RI}_6") (pintype "input"))
    )
    (net (code "116") (name "unconnected-(IC4-~{RTS}-Pad3)") (class "Default")
      (node (ref "IC4") (pin "3") (pinfunction "~{RTS}_3") (pintype "output"))
    )
    (net (code "117") (name "unconnected-(IC7-CBUS2-Pad13)") (class "Default")
      (node (ref "IC7") (pin "13") (pinfunction "CBUS2_13") (pintype "bidirectional"))
    )
    (net (code "118") (name "unconnected-(IC7-CBUS3-Pad14)") (class "Default")
      (node (ref "IC7") (pin "14") (pinfunction "CBUS3_14") (pintype "bidirectional"))
    )
    (net (code "119") (name "unconnected-(IC7-CBUS4-Pad12)") (class "Default")
      (node (ref "IC7") (pin "12") (pinfunction "CBUS4_12") (pintype "bidirectional"))
    )
    (net (code "120") (name "unconnected-(IC7-OSCI-Pad27)") (class "Default")
      (node (ref "IC7") (pin "27") (pinfunction "OSCI_27") (pintype "input"))
    )
    (net (code "121") (name "unconnected-(IC7-OSCO-Pad28)") (class "Default")
      (node (ref "IC7") (pin "28") (pinfunction "OSCO_28") (pintype "output"))
    )
    (net (code "122") (name "unconnected-(IC7-~{CTS}-Pad11)") (class "Default")
      (node (ref "IC7") (pin "11") (pinfunction "~{CTS}_11") (pintype "input"))
    )
    (net (code "123") (name "unconnected-(IC7-~{DCD}-Pad10)") (class "Default")
      (node (ref "IC7") (pin "10") (pinfunction "~{DCD}_10") (pintype "input"))
    )
    (net (code "124") (name "unconnected-(IC7-~{DSR}-Pad9)") (class "Default")
      (node (ref "IC7") (pin "9") (pinfunction "~{DSR}_9") (pintype "input"))
    )
    (net (code "125") (name "unconnected-(IC7-~{RI}-Pad6)") (class "Default")
      (node (ref "IC7") (pin "6") (pinfunction "~{RI}_6") (pintype "input"))
    )
    (net (code "126") (name "unconnected-(IC7-~{RTS}-Pad3)") (class "Default")
      (node (ref "IC7") (pin "3") (pinfunction "~{RTS}_3") (pintype "output"))
    )
    (net (code "127") (name "unconnected-(LED2-RED_A-Pad2)") (class "Default")
      (node (ref "LED2") (pin "2") (pinfunction "RED_A_2") (pintype "bidirectional"))
    )
    (net (code "128") (name "unconnected-(TIVA1-PadID)") (class "Default")
      (node (ref "TIVA1") (pin "ID") (pinfunction "ID_ID") (pintype "bidirectional"))
    )
    (net (code "129") (name "unconnected-(U$1-PadP$32)") (class "Default")
      (node (ref "U$1") (pin "P$32") (pinfunction "P$32_P$32") (pintype "bidirectional"))
    )
    (net (code "130") (name "unconnected-(U$1-PadP$36)") (class "Default")
      (node (ref "U$1") (pin "P$36") (pinfunction "P$36_P$36") (pintype "bidirectional"))
    )
    (net (code "131") (name "unconnected-(U$1-PadP$37)") (class "Default")
      (node (ref "U$1") (pin "P$37") (pinfunction "P$37_P$37") (pintype "bidirectional"))
    )
    (net (code "132") (name "unconnected-(U$4-P$3-PadP3)") (class "Default")
      (node (ref "U$4") (pin "P3") (pinfunction "P$3_P3") (pintype "bidirectional"))
    )
    (net (code "133") (name "unconnected-(U1-NC-1-Pad1)") (class "Default")
      (node (ref "U1") (pin "1") (pinfunction "NC-1_1") (pintype "no_connect"))
    )
    (net (code "134") (name "unconnected-(U1-NC-2-Pad2)") (class "Default")
      (node (ref "U1") (pin "2") (pinfunction "NC-2_2") (pintype "no_connect"))
    )
    (net (code "135") (name "unconnected-(U2-NC-1-Pad1)") (class "Default")
      (node (ref "U2") (pin "1") (pinfunction "NC-1_1") (pintype "no_connect"))
    )
    (net (code "136") (name "unconnected-(U2-NC-2-Pad2)") (class "Default")
      (node (ref "U2") (pin "2") (pinfunction "NC-2_2") (pintype "no_connect"))
    )
    (net (code "137") (name "unconnected-(U3-NC-1-Pad1)") (class "Default")
      (node (ref "U3") (pin "1") (pinfunction "NC-1_1") (pintype "no_connect"))
    )
    (net (code "138") (name "unconnected-(U3-NC-2-Pad2)") (class "Default")
      (node (ref "U3") (pin "2") (pinfunction "NC-2_2") (pintype "no_connect"))
    )
    (net (code "139") (name "unconnected-(U4-NC-1-Pad1)") (class "Default")
      (node (ref "U4") (pin "1") (pinfunction "NC-1_1") (pintype "no_connect"))
    )
    (net (code "140") (name "unconnected-(U4-NC-2-Pad2)") (class "Default")
      (node (ref "U4") (pin "2") (pinfunction "NC-2_2") (pintype "no_connect"))
    )
    (net (code "141") (name "unconnected-(U5-NC-1-Pad1)") (class "Default")
      (node (ref "U5") (pin "1") (pinfunction "NC-1_1") (pintype "no_connect"))
    )
    (net (code "142") (name "unconnected-(U5-NC-2-Pad2)") (class "Default")
      (node (ref "U5") (pin "2") (pinfunction "NC-2_2") (pintype "no_connect"))
    )
    (net (code "143") (name "unconnected-(U6-NC-1-Pad1)") (class "Default")
      (node (ref "U6") (pin "1") (pinfunction "NC-1_1") (pintype "no_connect"))
    )
    (net (code "144") (name "unconnected-(U6-NC-2-Pad2)") (class "Default")
      (node (ref "U6") (pin "2") (pinfunction "NC-2_2") (pintype "no_connect"))
    )
    (net (code "145") (name "unconnected-(U7-NC-1-Pad1)") (class "Default")
      (node (ref "U7") (pin "1") (pinfunction "NC-1_1") (pintype "no_connect"))
    )
    (net (code "146") (name "unconnected-(U7-NC-2-Pad2)") (class "Default")
      (node (ref "U7") (pin "2") (pinfunction "NC-2_2") (pintype "no_connect"))
    )
    (net (code "147") (name "unconnected-(XB1-AD0{slash}DIO0-Pad20)") (class "Default")
      (node (ref "XB1") (pin "20") (pinfunction "AD0/DIO0_20") (pintype "bidirectional"))
    )
    (net (code "148") (name "unconnected-(XB1-AD1{slash}DIO1-Pad19)") (class "Default")
      (node (ref "XB1") (pin "19") (pinfunction "AD1/DIO1_19") (pintype "bidirectional"))
    )
    (net (code "149") (name "unconnected-(XB1-AD2{slash}DIO2-Pad18)") (class "Default")
      (node (ref "XB1") (pin "18") (pinfunction "AD2/DIO2_18") (pintype "bidirectional"))
    )
    (net (code "150") (name "unconnected-(XB1-CD{slash}DOUT_EN{slash}DO8-Pad4)") (class "Default")
      (node (ref "XB1") (pin "4") (pinfunction "CD/DOUT_EN/DO8_4") (pintype "output"))
    )
    (net (code "151") (name "unconnected-(XB1-COORD_SEL{slash}AD3{slash}DIO3-Pad17)") (class "Default")
      (node (ref "XB1") (pin "17") (pinfunction "COORD_SEL/AD3/DIO3_17") (pintype "bidirectional"))
    )
    (net (code "152") (name "unconnected-(XB1-ON{slash}~{SLEEP}-Pad13)") (class "Default")
      (node (ref "XB1") (pin "13") (pinfunction "ON/~{SLEEP}_13") (pintype "output"))
    )
    (net (code "153") (name "unconnected-(XB1-RF_TX{slash}AD4{slash}DIO4-Pad11)") (class "Default")
      (node (ref "XB1") (pin "11") (pinfunction "RF_TX/AD4/DIO4_11") (pintype "bidirectional"))
    )
    (net (code "154") (name "unconnected-(XB1-VREF-Pad14)") (class "Default")
      (node (ref "XB1") (pin "14") (pinfunction "VREF_14") (pintype "input"))
    )
    (net (code "155") (name "unconnected-(XB1-~{CTS}{slash}DIO7-Pad12)") (class "Default")
      (node (ref "XB1") (pin "12") (pinfunction "~{CTS}/DIO7_12") (pintype "bidirectional"))
    )
    (net (code "156") (name "unconnected-(XB1-~{DTR}{slash}SLEEP_RQ{slash}DI8-Pad9)") (class "Default")
      (node (ref "XB1") (pin "9") (pinfunction "~{DTR}/SLEEP_RQ/DI8_9") (pintype "bidirectional"))
    )
    (net (code "157") (name "unconnected-(XB1-~{RESET}-Pad5)") (class "Default")
      (node (ref "XB1") (pin "5") (pinfunction "~{RESET}_5") (pintype "input"))
    )
    (net (code "158") (name "unconnected-(XB1-~{RTS}{slash}AD6{slash}DIO6-Pad16)") (class "Default")
      (node (ref "XB1") (pin "16") (pinfunction "~{RTS}/AD6/DIO6_16") (pintype "bidirectional"))
    )
  )
)
